# Led_Tree_Main.net
KiCad netlist of a schematic drawn in Altium Designer
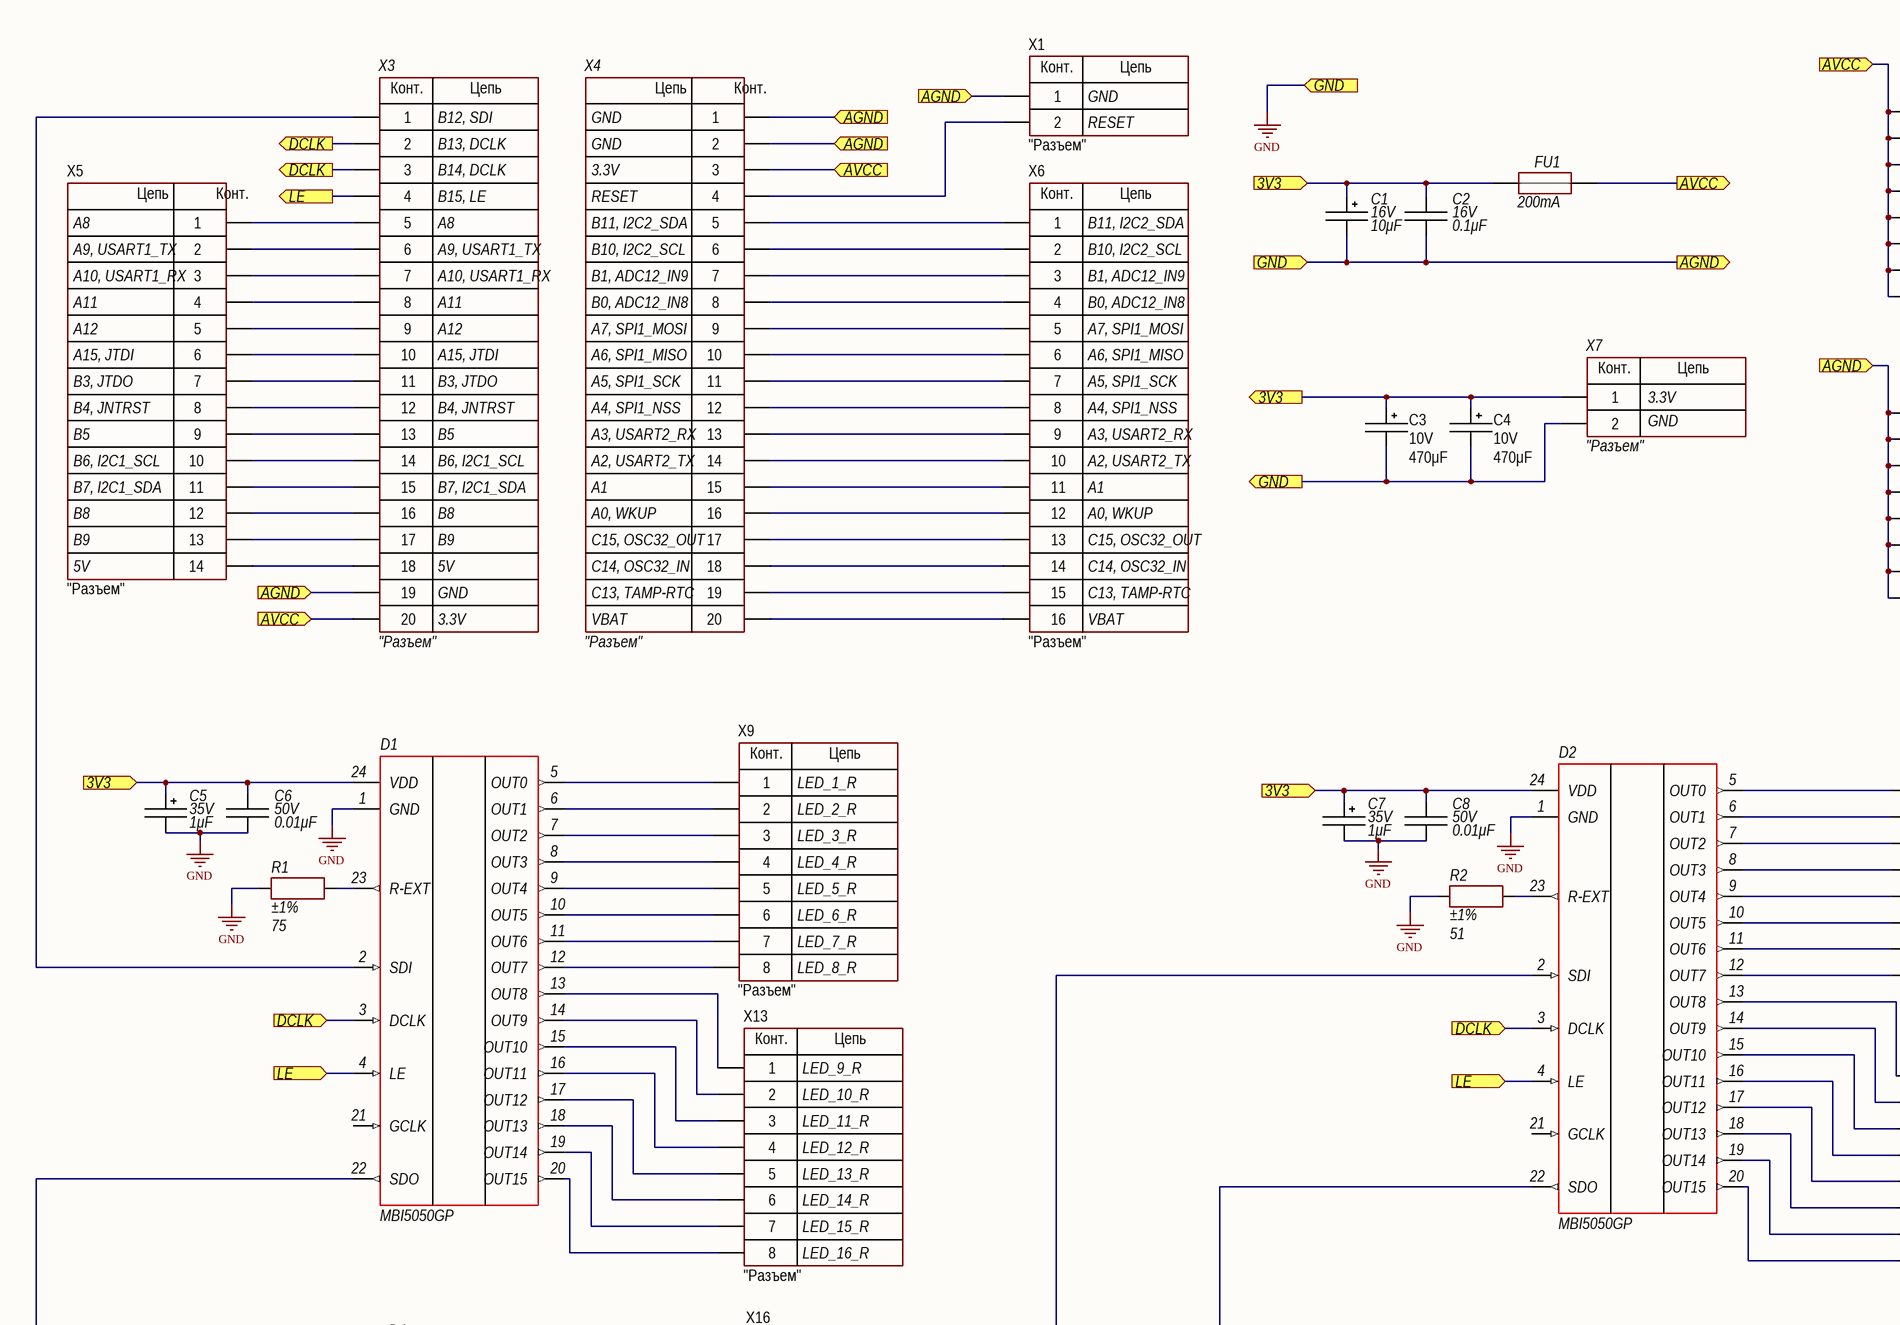
[diagram p0: Led_Tree_Main.SchDoc, top left]
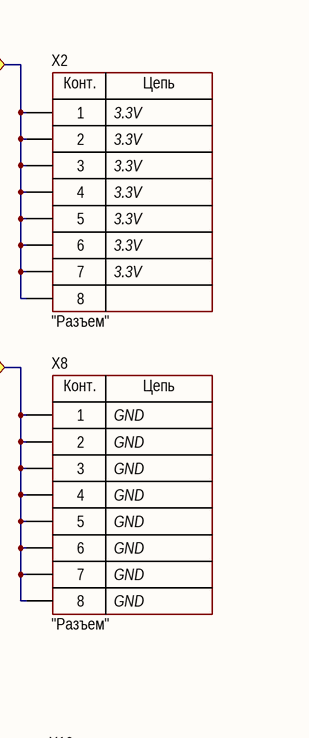
[diagram p1: Led_Tree_Main.SchDoc, top right]
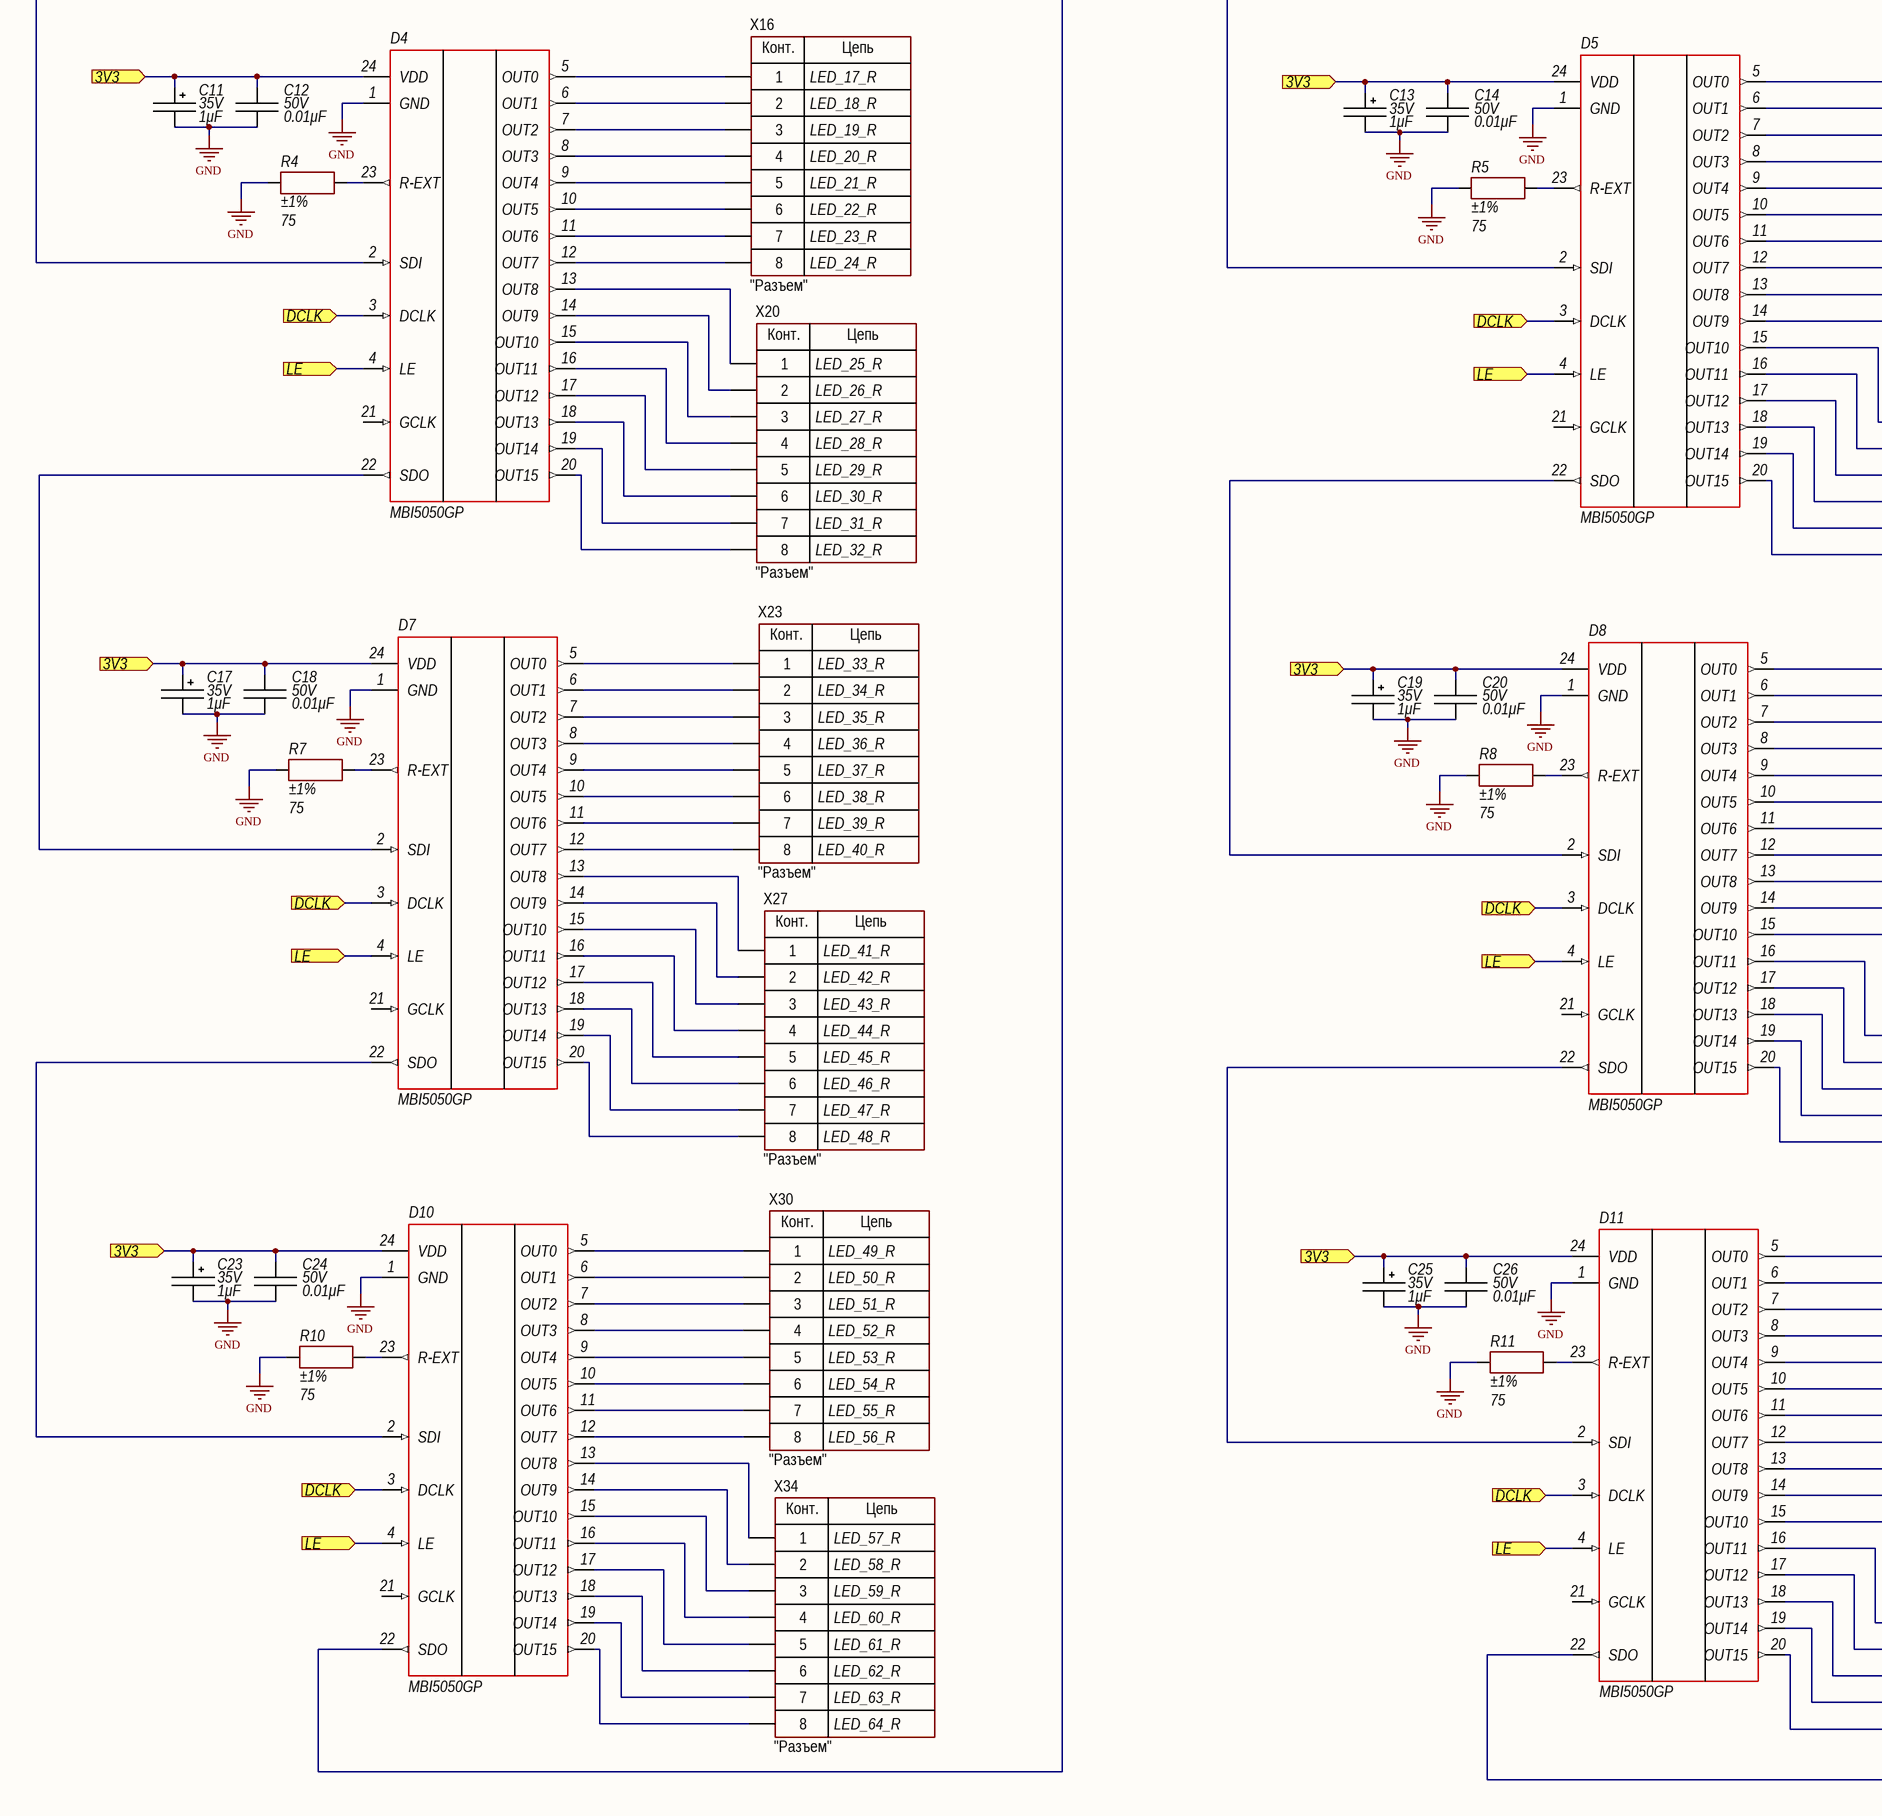
[diagram p2: Led_Tree_Main.SchDoc, bottom left]
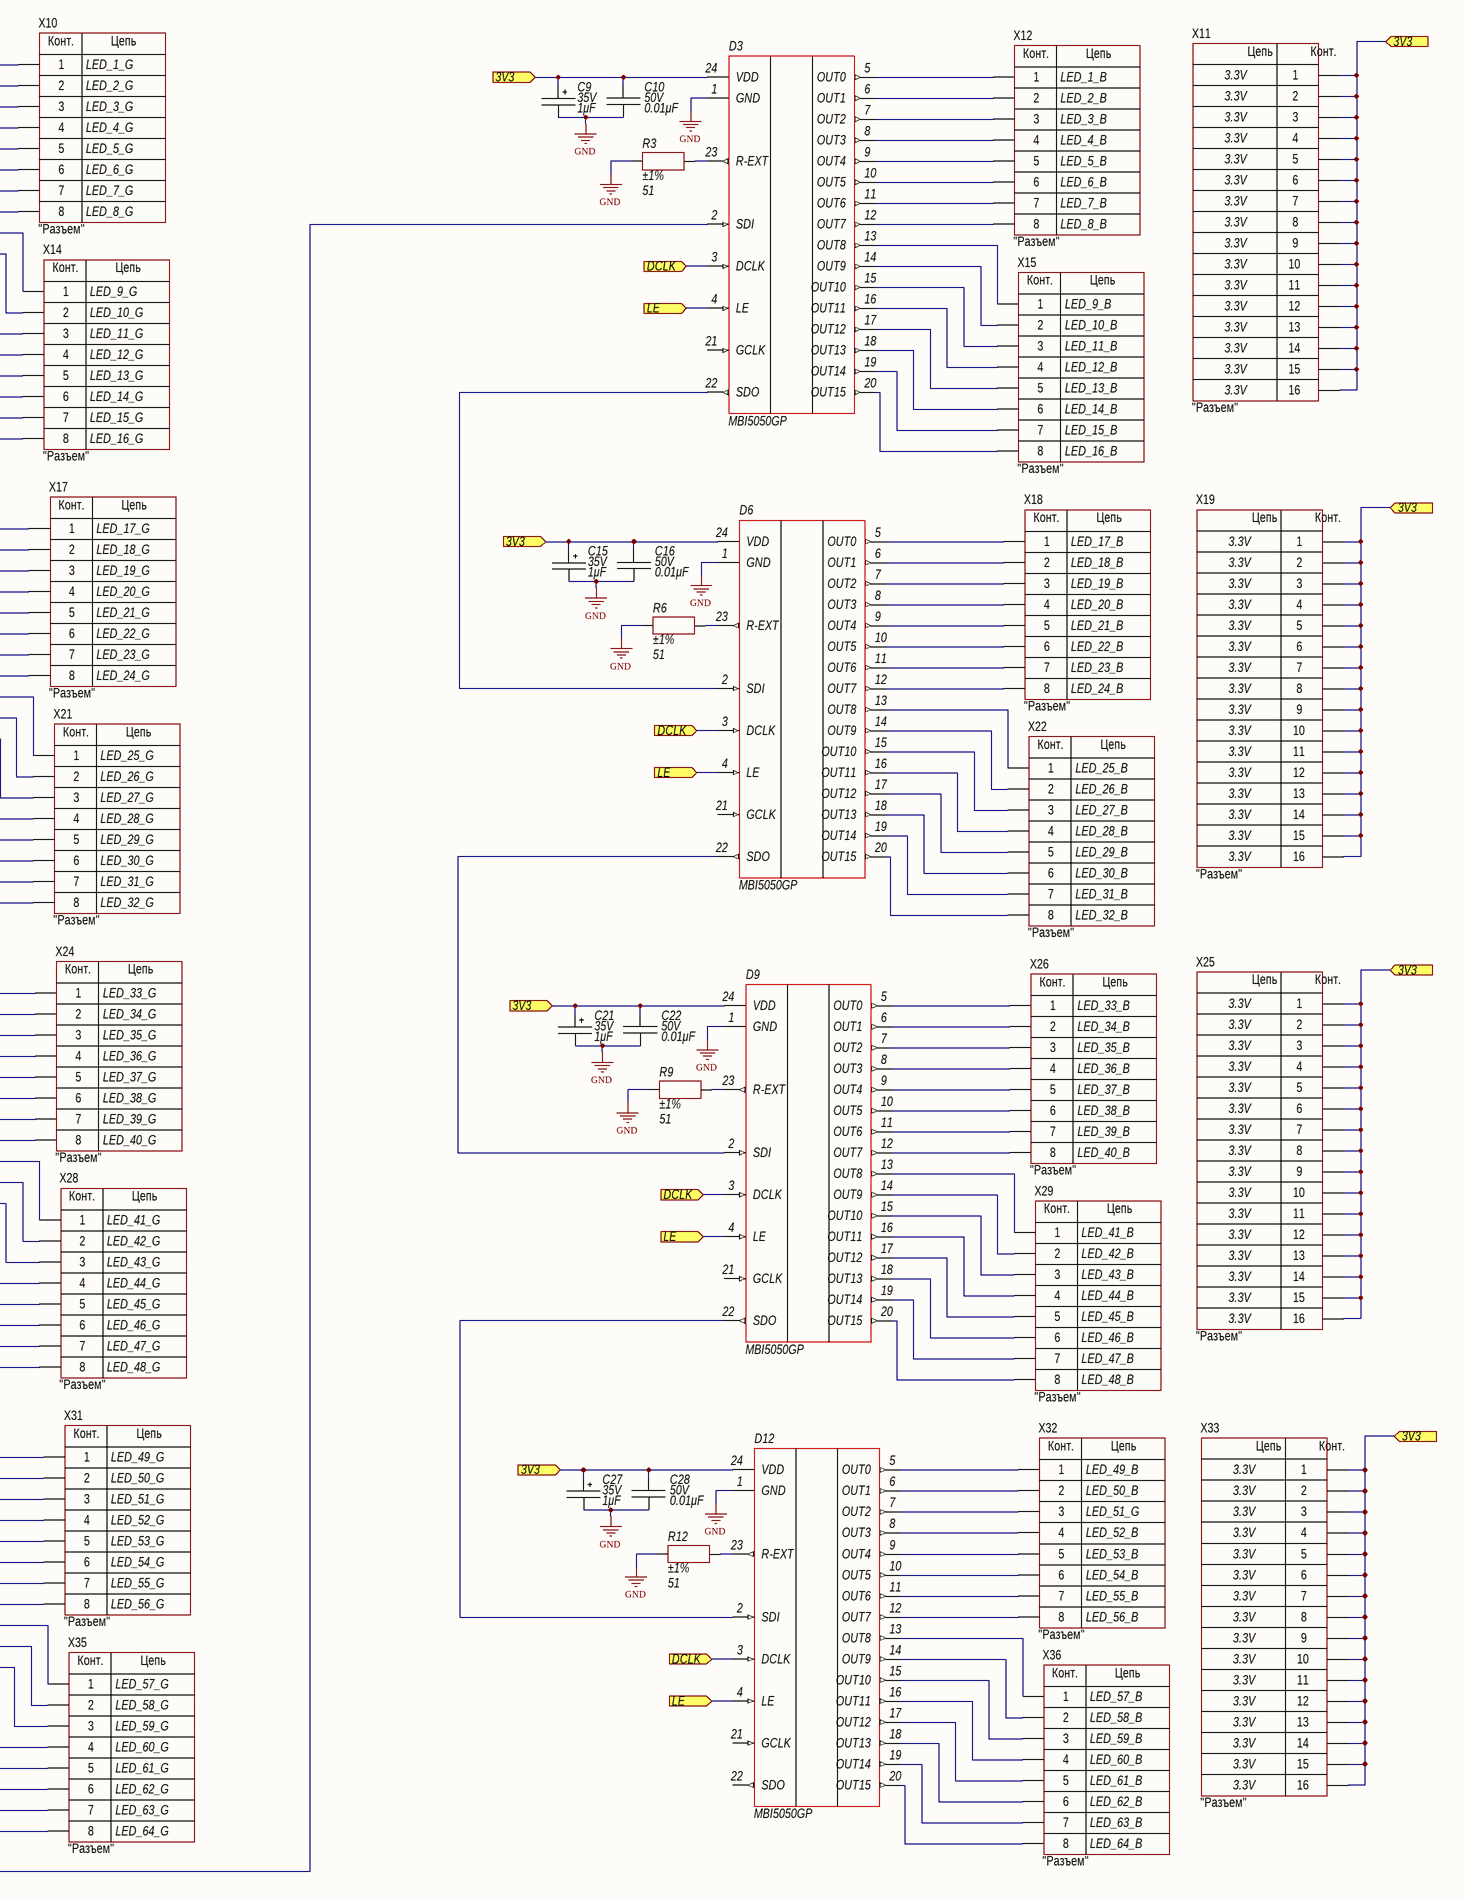
[diagram p3: Led_Tree_Main.SchDoc, bottom right]

(export (version "E")
  (design (tool "Eeschema 10.0.6"))
  (components
    (comp (ref "C1")
      (value "10μF")
      (footprint "CAP: TANTAL-A")
      (fields
        (field (name "MANUFACTURER") "AVX")
        (field (name "PARTNUMBER") "TAJA106K016RNJ")
        (field (name "VALUEMANUFACTURERPARTNUMBER") "Tantalum capacitor, 10μF, 16V, ±10%, 3Ohm, case A (3216), -55...+125°C")
        (field (name "VOLTAGE") "16V")
      )
      (libsource (lib "Capacitor") (part "Tantal_A"))
    )
    (comp (ref "C2")
      (value "0.1μF")
      (footprint "CAP: 0603")
      (fields
        (field (name "MANUFACTURER") "Murata Electronics")
        (field (name "PARTNUMBER") "GRM188R71C104KA01D")
        (field (name "VALUEMANUFACTURERPARTNUMBER") "Ceramic capacitor, 0.1μF, X7R, ±10%, 16V, 0603, -55...+125°C")
        (field (name "VOLTAGE") "16V")
      )
      (libsource (lib "Capacitor") (part "Ceramic_0603"))
    )
    (comp (ref "C3")
      (value "470μF")
      (footprint "CAP: D6.3C2.5H11")
      (fields
        (field (name "MANUFACTURER") "JB")
        (field (name "PARTNUMBER") "JRB1A471M02500630120000B")
        (field (name "VALUEMANUFACTURERPARTNUMBER") "Aluminium capacitor, 470μF, 10V, ±20%, , 14x10x5 mm, -40...+105°C")
        (field (name "VOLTAGE") "10V")
      )
      (libsource (lib "Capacitor") (part "Aluminium"))
    )
    (comp (ref "C4")
      (value "470μF")
      (footprint "CAP: D6.3C2.5H11")
      (fields
        (field (name "MANUFACTURER") "JB")
        (field (name "PARTNUMBER") "JRB1A471M02500630120000B")
        (field (name "VALUEMANUFACTURERPARTNUMBER") "Aluminium capacitor, 470μF, 10V, ±20%, , 14x10x5 mm, -40...+105°C")
        (field (name "VOLTAGE") "10V")
      )
      (libsource (lib "Capacitor") (part "Aluminium"))
    )
    (comp (ref "C5")
      (value "1μF")
      (footprint "CAP: TANTAL-A")
      (fields
        (field (name "MANUFACTURER") "AVX")
        (field (name "PARTNUMBER") "TAJA105K035RNJ")
        (field (name "VALUEMANUFACTURERPARTNUMBER") "Tantalum capacitor, 1μF, 35V, ±10%, 7.5Ohm, case A (3216), -55...+125°C")
        (field (name "VOLTAGE") "35V")
      )
      (libsource (lib "Capacitor") (part "Tantal_A"))
    )
    (comp (ref "C6")
      (value "0.01μF")
      (footprint "CAP: 0603")
      (fields
        (field (name "MANUFACTURER") "Murata Electronics")
        (field (name "PARTNUMBER") "GRM188R71H103KA01D")
        (field (name "VALUEMANUFACTURERPARTNUMBER") "Ceramic capacitor, 0.01μF, X7R, ±10%, 50V, 0603, -55...+125°C")
        (field (name "VOLTAGE") "50V")
      )
      (libsource (lib "Capacitor") (part "Ceramic_0603"))
    )
    (comp (ref "C7")
      (value "1μF")
      (footprint "CAP: TANTAL-A")
      (fields
        (field (name "MANUFACTURER") "AVX")
        (field (name "PARTNUMBER") "TAJA105K035RNJ")
        (field (name "VALUEMANUFACTURERPARTNUMBER") "Tantalum capacitor, 1μF, 35V, ±10%, 7.5Ohm, case A (3216), -55...+125°C")
        (field (name "VOLTAGE") "35V")
      )
      (libsource (lib "Capacitor") (part "Tantal_A"))
    )
    (comp (ref "C8")
      (value "0.01μF")
      (footprint "CAP: 0603")
      (fields
        (field (name "MANUFACTURER") "Murata Electronics")
        (field (name "PARTNUMBER") "GRM188R71H103KA01D")
        (field (name "VALUEMANUFACTURERPARTNUMBER") "Ceramic capacitor, 0.01μF, X7R, ±10%, 50V, 0603, -55...+125°C")
        (field (name "VOLTAGE") "50V")
      )
      (libsource (lib "Capacitor") (part "Ceramic_0603"))
    )
    (comp (ref "C9")
      (value "1μF")
      (footprint "CAP: TANTAL-A")
      (fields
        (field (name "MANUFACTURER") "AVX")
        (field (name "PARTNUMBER") "TAJA105K035RNJ")
        (field (name "VALUEMANUFACTURERPARTNUMBER") "Tantalum capacitor, 1μF, 35V, ±10%, 7.5Ohm, case A (3216), -55...+125°C")
        (field (name "VOLTAGE") "35V")
      )
      (libsource (lib "Capacitor") (part "Tantal_A"))
    )
    (comp (ref "C10")
      (value "0.01μF")
      (footprint "CAP: 0603")
      (fields
        (field (name "MANUFACTURER") "Murata Electronics")
        (field (name "PARTNUMBER") "GRM188R71H103KA01D")
        (field (name "VALUEMANUFACTURERPARTNUMBER") "Ceramic capacitor, 0.01μF, X7R, ±10%, 50V, 0603, -55...+125°C")
        (field (name "VOLTAGE") "50V")
      )
      (libsource (lib "Capacitor") (part "Ceramic_0603"))
    )
    (comp (ref "C11")
      (value "1μF")
      (footprint "CAP: TANTAL-A")
      (fields
        (field (name "MANUFACTURER") "AVX")
        (field (name "PARTNUMBER") "TAJA105K035RNJ")
        (field (name "VALUEMANUFACTURERPARTNUMBER") "Tantalum capacitor, 1μF, 35V, ±10%, 7.5Ohm, case A (3216), -55...+125°C")
        (field (name "VOLTAGE") "35V")
      )
      (libsource (lib "Capacitor") (part "Tantal_A"))
    )
    (comp (ref "C12")
      (value "0.01μF")
      (footprint "CAP: 0603")
      (fields
        (field (name "MANUFACTURER") "Murata Electronics")
        (field (name "PARTNUMBER") "GRM188R71H103KA01D")
        (field (name "VALUEMANUFACTURERPARTNUMBER") "Ceramic capacitor, 0.01μF, X7R, ±10%, 50V, 0603, -55...+125°C")
        (field (name "VOLTAGE") "50V")
      )
      (libsource (lib "Capacitor") (part "Ceramic_0603"))
    )
    (comp (ref "C13")
      (value "1μF")
      (footprint "CAP: TANTAL-A")
      (fields
        (field (name "MANUFACTURER") "AVX")
        (field (name "PARTNUMBER") "TAJA105K035RNJ")
        (field (name "VALUEMANUFACTURERPARTNUMBER") "Tantalum capacitor, 1μF, 35V, ±10%, 7.5Ohm, case A (3216), -55...+125°C")
        (field (name "VOLTAGE") "35V")
      )
      (libsource (lib "Capacitor") (part "Tantal_A"))
    )
    (comp (ref "C14")
      (value "0.01μF")
      (footprint "CAP: 0603")
      (fields
        (field (name "MANUFACTURER") "Murata Electronics")
        (field (name "PARTNUMBER") "GRM188R71H103KA01D")
        (field (name "VALUEMANUFACTURERPARTNUMBER") "Ceramic capacitor, 0.01μF, X7R, ±10%, 50V, 0603, -55...+125°C")
        (field (name "VOLTAGE") "50V")
      )
      (libsource (lib "Capacitor") (part "Ceramic_0603"))
    )
    (comp (ref "C15")
      (value "1μF")
      (footprint "CAP: TANTAL-A")
      (fields
        (field (name "MANUFACTURER") "AVX")
        (field (name "PARTNUMBER") "TAJA105K035RNJ")
        (field (name "VALUEMANUFACTURERPARTNUMBER") "Tantalum capacitor, 1μF, 35V, ±10%, 7.5Ohm, case A (3216), -55...+125°C")
        (field (name "VOLTAGE") "35V")
      )
      (libsource (lib "Capacitor") (part "Tantal_A"))
    )
    (comp (ref "C16")
      (value "0.01μF")
      (footprint "CAP: 0603")
      (fields
        (field (name "MANUFACTURER") "Murata Electronics")
        (field (name "PARTNUMBER") "GRM188R71H103KA01D")
        (field (name "VALUEMANUFACTURERPARTNUMBER") "Ceramic capacitor, 0.01μF, X7R, ±10%, 50V, 0603, -55...+125°C")
        (field (name "VOLTAGE") "50V")
      )
      (libsource (lib "Capacitor") (part "Ceramic_0603"))
    )
    (comp (ref "C17")
      (value "1μF")
      (footprint "CAP: TANTAL-A")
      (fields
        (field (name "MANUFACTURER") "AVX")
        (field (name "PARTNUMBER") "TAJA105K035RNJ")
        (field (name "VALUEMANUFACTURERPARTNUMBER") "Tantalum capacitor, 1μF, 35V, ±10%, 7.5Ohm, case A (3216), -55...+125°C")
        (field (name "VOLTAGE") "35V")
      )
      (libsource (lib "Capacitor") (part "Tantal_A"))
    )
    (comp (ref "C18")
      (value "0.01μF")
      (footprint "CAP: 0603")
      (fields
        (field (name "MANUFACTURER") "Murata Electronics")
        (field (name "PARTNUMBER") "GRM188R71H103KA01D")
        (field (name "VALUEMANUFACTURERPARTNUMBER") "Ceramic capacitor, 0.01μF, X7R, ±10%, 50V, 0603, -55...+125°C")
        (field (name "VOLTAGE") "50V")
      )
      (libsource (lib "Capacitor") (part "Ceramic_0603"))
    )
    (comp (ref "C19")
      (value "1μF")
      (footprint "CAP: TANTAL-A")
      (fields
        (field (name "MANUFACTURER") "AVX")
        (field (name "PARTNUMBER") "TAJA105K035RNJ")
        (field (name "VALUEMANUFACTURERPARTNUMBER") "Tantalum capacitor, 1μF, 35V, ±10%, 7.5Ohm, case A (3216), -55...+125°C")
        (field (name "VOLTAGE") "35V")
      )
      (libsource (lib "Capacitor") (part "Tantal_A"))
    )
    (comp (ref "C20")
      (value "0.01μF")
      (footprint "CAP: 0603")
      (fields
        (field (name "MANUFACTURER") "Murata Electronics")
        (field (name "PARTNUMBER") "GRM188R71H103KA01D")
        (field (name "VALUEMANUFACTURERPARTNUMBER") "Ceramic capacitor, 0.01μF, X7R, ±10%, 50V, 0603, -55...+125°C")
        (field (name "VOLTAGE") "50V")
      )
      (libsource (lib "Capacitor") (part "Ceramic_0603"))
    )
    (comp (ref "C21")
      (value "1μF")
      (footprint "CAP: TANTAL-A")
      (fields
        (field (name "MANUFACTURER") "AVX")
        (field (name "PARTNUMBER") "TAJA105K035RNJ")
        (field (name "VALUEMANUFACTURERPARTNUMBER") "Tantalum capacitor, 1μF, 35V, ±10%, 7.5Ohm, case A (3216), -55...+125°C")
        (field (name "VOLTAGE") "35V")
      )
      (libsource (lib "Capacitor") (part "Tantal_A"))
    )
    (comp (ref "C22")
      (value "0.01μF")
      (footprint "CAP: 0603")
      (fields
        (field (name "MANUFACTURER") "Murata Electronics")
        (field (name "PARTNUMBER") "GRM188R71H103KA01D")
        (field (name "VALUEMANUFACTURERPARTNUMBER") "Ceramic capacitor, 0.01μF, X7R, ±10%, 50V, 0603, -55...+125°C")
        (field (name "VOLTAGE") "50V")
      )
      (libsource (lib "Capacitor") (part "Ceramic_0603"))
    )
    (comp (ref "C23")
      (value "1μF")
      (footprint "CAP: TANTAL-A")
      (fields
        (field (name "MANUFACTURER") "AVX")
        (field (name "PARTNUMBER") "TAJA105K035RNJ")
        (field (name "VALUEMANUFACTURERPARTNUMBER") "Tantalum capacitor, 1μF, 35V, ±10%, 7.5Ohm, case A (3216), -55...+125°C")
        (field (name "VOLTAGE") "35V")
      )
      (libsource (lib "Capacitor") (part "Tantal_A"))
    )
    (comp (ref "C24")
      (value "0.01μF")
      (footprint "CAP: 0603")
      (fields
        (field (name "MANUFACTURER") "Murata Electronics")
        (field (name "PARTNUMBER") "GRM188R71H103KA01D")
        (field (name "VALUEMANUFACTURERPARTNUMBER") "Ceramic capacitor, 0.01μF, X7R, ±10%, 50V, 0603, -55...+125°C")
        (field (name "VOLTAGE") "50V")
      )
      (libsource (lib "Capacitor") (part "Ceramic_0603"))
    )
    (comp (ref "C25")
      (value "1μF")
      (footprint "CAP: TANTAL-A")
      (fields
        (field (name "MANUFACTURER") "AVX")
        (field (name "PARTNUMBER") "TAJA105K035RNJ")
        (field (name "VALUEMANUFACTURERPARTNUMBER") "Tantalum capacitor, 1μF, 35V, ±10%, 7.5Ohm, case A (3216), -55...+125°C")
        (field (name "VOLTAGE") "35V")
      )
      (libsource (lib "Capacitor") (part "Tantal_A"))
    )
    (comp (ref "C26")
      (value "0.01μF")
      (footprint "CAP: 0603")
      (fields
        (field (name "MANUFACTURER") "Murata Electronics")
        (field (name "PARTNUMBER") "GRM188R71H103KA01D")
        (field (name "VALUEMANUFACTURERPARTNUMBER") "Ceramic capacitor, 0.01μF, X7R, ±10%, 50V, 0603, -55...+125°C")
        (field (name "VOLTAGE") "50V")
      )
      (libsource (lib "Capacitor") (part "Ceramic_0603"))
    )
    (comp (ref "C27")
      (value "1μF")
      (footprint "CAP: TANTAL-A")
      (fields
        (field (name "MANUFACTURER") "AVX")
        (field (name "PARTNUMBER") "TAJA105K035RNJ")
        (field (name "VALUEMANUFACTURERPARTNUMBER") "Tantalum capacitor, 1μF, 35V, ±10%, 7.5Ohm, case A (3216), -55...+125°C")
        (field (name "VOLTAGE") "35V")
      )
      (libsource (lib "Capacitor") (part "Tantal_A"))
    )
    (comp (ref "C28")
      (value "0.01μF")
      (footprint "CAP: 0603")
      (fields
        (field (name "MANUFACTURER") "Murata Electronics")
        (field (name "PARTNUMBER") "GRM188R71H103KA01D")
        (field (name "VALUEMANUFACTURERPARTNUMBER") "Ceramic capacitor, 0.01μF, X7R, ±10%, 50V, 0603, -55...+125°C")
        (field (name "VOLTAGE") "50V")
      )
      (libsource (lib "Capacitor") (part "Ceramic_0603"))
    )
    (comp (ref "D1")
      (value "MBI5050GP")
      (footprint "MBI5050GP")
      (description "16ch PWM LED Driver")
      (libsource (lib "LED_Drivers") (part "MBI5050GP"))
    )
    (comp (ref "D2")
      (value "MBI5050GP")
      (footprint "MBI5050GP")
      (description "16ch PWM LED Driver")
      (libsource (lib "LED_Drivers") (part "MBI5050GP"))
    )
    (comp (ref "D3")
      (value "MBI5050GP")
      (footprint "MBI5050GP")
      (description "16ch PWM LED Driver")
      (libsource (lib "LED_Drivers") (part "MBI5050GP"))
    )
    (comp (ref "D4")
      (value "MBI5050GP")
      (footprint "MBI5050GP")
      (description "16ch PWM LED Driver")
      (libsource (lib "LED_Drivers") (part "MBI5050GP"))
    )
    (comp (ref "D5")
      (value "MBI5050GP")
      (footprint "MBI5050GP")
      (description "16ch PWM LED Driver")
      (libsource (lib "LED_Drivers") (part "MBI5050GP"))
    )
    (comp (ref "D6")
      (value "MBI5050GP")
      (footprint "MBI5050GP")
      (description "16ch PWM LED Driver")
      (libsource (lib "LED_Drivers") (part "MBI5050GP"))
    )
    (comp (ref "D7")
      (value "MBI5050GP")
      (footprint "MBI5050GP")
      (description "16ch PWM LED Driver")
      (libsource (lib "LED_Drivers") (part "MBI5050GP"))
    )
    (comp (ref "D8")
      (value "MBI5050GP")
      (footprint "MBI5050GP")
      (description "16ch PWM LED Driver")
      (libsource (lib "LED_Drivers") (part "MBI5050GP"))
    )
    (comp (ref "D9")
      (value "MBI5050GP")
      (footprint "MBI5050GP")
      (description "16ch PWM LED Driver")
      (libsource (lib "LED_Drivers") (part "MBI5050GP"))
    )
    (comp (ref "D10")
      (value "MBI5050GP")
      (footprint "MBI5050GP")
      (description "16ch PWM LED Driver")
      (libsource (lib "LED_Drivers") (part "MBI5050GP"))
    )
    (comp (ref "D11")
      (value "MBI5050GP")
      (footprint "MBI5050GP")
      (description "16ch PWM LED Driver")
      (libsource (lib "LED_Drivers") (part "MBI5050GP"))
    )
    (comp (ref "D12")
      (value "MBI5050GP")
      (footprint "MBI5050GP")
      (description "16ch PWM LED Driver")
      (libsource (lib "LED_Drivers") (part "MBI5050GP"))
    )
    (comp (ref "FU1") (value "200mA") (footprint "1210L020WR") (libsource (lib "Fuses") (part "1210L020WR")))
    (comp (ref "R1")
      (value "75")
      (footprint "RES: 0603")
      (fields
        (field (name "MANUFACTURER") "Yageo")
        (field (name "PARTNUMBER") "RC0603FR-0775RL")
        (field (name "VALUEMANUFACTURERPARTNUMBER") "Resistor film, 75, ±1%, 0603, 0.1W, -55...+155°C")
        (field (name "TOLERANCE") "±1%")
      )
      (libsource (lib "Resistor") (part "Resistor_0603"))
    )
    (comp (ref "R2")
      (value "51")
      (footprint "RES: 0603")
      (fields
        (field (name "MANUFACTURER") "Yageo")
        (field (name "PARTNUMBER") "RC0603FR-0751RL")
        (field (name "VALUEMANUFACTURERPARTNUMBER") "Resistor film, 51, ±1%, 0603, 0.1W, -55...+155°C")
        (field (name "TOLERANCE") "±1%")
      )
      (libsource (lib "Resistor") (part "Resistor_0603"))
    )
    (comp (ref "R3")
      (value "51")
      (footprint "RES: 0603")
      (fields
        (field (name "MANUFACTURER") "Yageo")
        (field (name "PARTNUMBER") "RC0603FR-0751RL")
        (field (name "VALUEMANUFACTURERPARTNUMBER") "Resistor film, 51, ±1%, 0603, 0.1W, -55...+155°C")
        (field (name "TOLERANCE") "±1%")
      )
      (libsource (lib "Resistor") (part "Resistor_0603"))
    )
    (comp (ref "R4")
      (value "75")
      (footprint "RES: 0603")
      (fields
        (field (name "MANUFACTURER") "Yageo")
        (field (name "PARTNUMBER") "RC0603FR-0775RL")
        (field (name "VALUEMANUFACTURERPARTNUMBER") "Resistor film, 75, ±1%, 0603, 0.1W, -55...+155°C")
        (field (name "TOLERANCE") "±1%")
      )
      (libsource (lib "Resistor") (part "Resistor_0603"))
    )
    (comp (ref "R5")
      (value "75")
      (footprint "RES: 0603")
      (fields
        (field (name "MANUFACTURER") "Yageo")
        (field (name "PARTNUMBER") "RC0603FR-0775RL")
        (field (name "VALUEMANUFACTURERPARTNUMBER") "Resistor film, 75, ±1%, 0603, 0.1W, -55...+155°C")
        (field (name "TOLERANCE") "±1%")
      )
      (libsource (lib "Resistor") (part "Resistor_0603"))
    )
    (comp (ref "R6")
      (value "51")
      (footprint "RES: 0603")
      (fields
        (field (name "MANUFACTURER") "Yageo")
        (field (name "PARTNUMBER") "RC0603FR-0751RL")
        (field (name "VALUEMANUFACTURERPARTNUMBER") "Resistor film, 51, ±1%, 0603, 0.1W, -55...+155°C")
        (field (name "TOLERANCE") "±1%")
      )
      (libsource (lib "Resistor") (part "Resistor_0603"))
    )
    (comp (ref "R7")
      (value "75")
      (footprint "RES: 0603")
      (fields
        (field (name "MANUFACTURER") "Yageo")
        (field (name "PARTNUMBER") "RC0603FR-0775RL")
        (field (name "VALUEMANUFACTURERPARTNUMBER") "Resistor film, 75, ±1%, 0603, 0.1W, -55...+155°C")
        (field (name "TOLERANCE") "±1%")
      )
      (libsource (lib "Resistor") (part "Resistor_0603"))
    )
    (comp (ref "R8")
      (value "75")
      (footprint "RES: 0603")
      (fields
        (field (name "MANUFACTURER") "Yageo")
        (field (name "PARTNUMBER") "RC0603FR-0775RL")
        (field (name "VALUEMANUFACTURERPARTNUMBER") "Resistor film, 75, ±1%, 0603, 0.1W, -55...+155°C")
        (field (name "TOLERANCE") "±1%")
      )
      (libsource (lib "Resistor") (part "Resistor_0603"))
    )
    (comp (ref "R9")
      (value "51")
      (footprint "RES: 0603")
      (fields
        (field (name "MANUFACTURER") "Yageo")
        (field (name "PARTNUMBER") "RC0603FR-0751RL")
        (field (name "VALUEMANUFACTURERPARTNUMBER") "Resistor film, 51, ±1%, 0603, 0.1W, -55...+155°C")
        (field (name "TOLERANCE") "±1%")
      )
      (libsource (lib "Resistor") (part "Resistor_0603"))
    )
    (comp (ref "R10")
      (value "75")
      (footprint "RES: 0603")
      (fields
        (field (name "MANUFACTURER") "Yageo")
        (field (name "PARTNUMBER") "RC0603FR-0775RL")
        (field (name "VALUEMANUFACTURERPARTNUMBER") "Resistor film, 75, ±1%, 0603, 0.1W, -55...+155°C")
        (field (name "TOLERANCE") "±1%")
      )
      (libsource (lib "Resistor") (part "Resistor_0603"))
    )
    (comp (ref "R11")
      (value "75")
      (footprint "RES: 0603")
      (fields
        (field (name "MANUFACTURER") "Yageo")
        (field (name "PARTNUMBER") "RC0603FR-0775RL")
        (field (name "VALUEMANUFACTURERPARTNUMBER") "Resistor film, 75, ±1%, 0603, 0.1W, -55...+155°C")
        (field (name "TOLERANCE") "±1%")
      )
      (libsource (lib "") (part "Resistor_0603_1"))
    )
    (comp (ref "R12")
      (value "51")
      (footprint "RES: 0603")
      (fields
        (field (name "MANUFACTURER") "Yageo")
        (field (name "PARTNUMBER") "RC0603FR-0751RL")
        (field (name "VALUEMANUFACTURERPARTNUMBER") "Resistor film, 51, ±1%, 0603, 0.1W, -55...+155°C")
        (field (name "TOLERANCE") "±1%")
      )
      (libsource (lib "Resistor") (part "Resistor_0603"))
    )
    (comp (ref "X1")
      (value "~")
      (footprint "CON: PLS-2")
      (fields
        (field (name "MANUFACTURER") "Connfly")
        (field (name "VALUEMANUFACTURERPARTNUMBER") "Connector, 2pin, 2.54mm, 500VAC, 3A")
        (field (name "PARTNUMBER") "PLS-2")
        (field (name "COMMENTTEXT") "\"Разъем\"")
      )
      (libsource (lib "Connector") (part "PLS-2"))
    )
    (comp (ref "X2")
      (value "~")
      (footprint "CON: PLS-8")
      (fields
        (field (name "MANUFACTURER") "Connfly")
        (field (name "VALUEMANUFACTURERPARTNUMBER") "Connector, 8pin, 2.54mm, 500VAC, 3A")
        (field (name "PARTNUMBER") "PLS-8")
        (field (name "COMMENTTEXT") "\"Разъем\"")
      )
      (libsource (lib "Connector") (part "PLS-8"))
    )
    (comp (ref "X3")
      (value "~")
      (footprint "CON: PBS-20")
      (fields
        (field (name "MANUFACTURER") "Connfly")
        (field (name "PARTNUMBER") "PBS-20")
        (field (name "VALUEMANUFACTURERPARTNUMBER") "Connector, 20pin, 2.54mm, 500VAC, 3A")
        (field (name "COMMENTTEXT") "\"Разъем\"")
      )
      (libsource (lib "Connector") (part "PBS-20"))
    )
    (comp (ref "X4")
      (value "~")
      (footprint "CON: PBS-20")
      (fields
        (field (name "MANUFACTURER") "Connfly")
        (field (name "PARTNUMBER") "PBS-20")
        (field (name "VALUEMANUFACTURERPARTNUMBER") "Connector, 20pin, 2.54mm, 500VAC, 3A")
        (field (name "COMMENTTEXT") "\"Разъем\"")
      )
      (libsource (lib "") (part "PBS-20_1"))
    )
    (comp (ref "X5")
      (value "~")
      (footprint "CON: PLS-14")
      (fields
        (field (name "MANUFACTURER") "Connfly")
        (field (name "VALUEMANUFACTURERPARTNUMBER") "Connector, 14pin, 2.54mm, 500VAC, 3A")
        (field (name "PARTNUMBER") "PLS-14")
        (field (name "COMMENTTEXT") "\"Разъем\"")
      )
      (libsource (lib "Connector") (part "PLS-14"))
    )
    (comp (ref "X6")
      (value "~")
      (footprint "CON: PLS-16")
      (fields
        (field (name "MANUFACTURER") "Connfly")
        (field (name "VALUEMANUFACTURERPARTNUMBER") "Connector, 16pin, 2.54mm, 500VAC, 3A")
        (field (name "PARTNUMBER") "PLS-16")
        (field (name "COMMENTTEXT") "\"Разъем\"")
      )
      (libsource (lib "Connector") (part "PLS-16"))
    )
    (comp (ref "X7")
      (value "~")
      (footprint "CON: TE 1-770166-0")
      (description "Power plug, to board, 2 pins")
      (fields
        (field (name "MANUFACTURER") "TE Connectivity")
        (field (name "PARTNUMBER") "1-770166-0")
        (field (name "COMMENTTEXT") "\"Разъем\"")
      )
      (libsource (lib "Connector") (part "TE 1-770166-0"))
    )
    (comp (ref "X8")
      (value "~")
      (footprint "CON: PLS-8")
      (fields
        (field (name "MANUFACTURER") "Connfly")
        (field (name "VALUEMANUFACTURERPARTNUMBER") "Connector, 8pin, 2.54mm, 500VAC, 3A")
        (field (name "PARTNUMBER") "PLS-8")
        (field (name "COMMENTTEXT") "\"Разъем\"")
      )
      (libsource (lib "Connector") (part "PLS-8"))
    )
    (comp (ref "X9")
      (value "~")
      (footprint "CON: PBS-8")
      (fields
        (field (name "MANUFACTURER") "Connfly")
        (field (name "VALUEMANUFACTURERPARTNUMBER") "Connector, 8pin, 2.54mm, 500VAC, 3A")
        (field (name "PARTNUMBER") "PBS-8")
        (field (name "COMMENTTEXT") "\"Разъем\"")
      )
      (libsource (lib "Connector") (part "PBS-8"))
    )
    (comp (ref "X10")
      (value "~")
      (footprint "CON: PBS-8")
      (fields
        (field (name "MANUFACTURER") "Connfly")
        (field (name "VALUEMANUFACTURERPARTNUMBER") "Connector, 8pin, 2.54mm, 500VAC, 3A")
        (field (name "PARTNUMBER") "PBS-8")
        (field (name "COMMENTTEXT") "\"Разъем\"")
      )
      (libsource (lib "Connector") (part "PBS-8"))
    )
    (comp (ref "X11")
      (value "~")
      (footprint "CON: PBS-16")
      (fields
        (field (name "MANUFACTURER") "Connfly")
        (field (name "VALUEMANUFACTURERPARTNUMBER") "Connector, 16pin, 2.54mm, 500VAC, 3A")
        (field (name "PARTNUMBER") "PBS-16")
        (field (name "COMMENTTEXT") "\"Разъем\"")
      )
      (libsource (lib "Connector") (part "PBS-16"))
    )
    (comp (ref "X12")
      (value "~")
      (footprint "CON: PBS-8")
      (fields
        (field (name "MANUFACTURER") "Connfly")
        (field (name "VALUEMANUFACTURERPARTNUMBER") "Connector, 8pin, 2.54mm, 500VAC, 3A")
        (field (name "PARTNUMBER") "PBS-8")
        (field (name "COMMENTTEXT") "\"Разъем\"")
      )
      (libsource (lib "Connector") (part "PBS-8"))
    )
    (comp (ref "X13")
      (value "~")
      (footprint "CON: PBS-8")
      (fields
        (field (name "MANUFACTURER") "Connfly")
        (field (name "VALUEMANUFACTURERPARTNUMBER") "Connector, 8pin, 2.54mm, 500VAC, 3A")
        (field (name "PARTNUMBER") "PBS-8")
        (field (name "COMMENTTEXT") "\"Разъем\"")
      )
      (libsource (lib "Connector") (part "PBS-8"))
    )
    (comp (ref "X14")
      (value "~")
      (footprint "CON: PBS-8")
      (fields
        (field (name "MANUFACTURER") "Connfly")
        (field (name "VALUEMANUFACTURERPARTNUMBER") "Connector, 8pin, 2.54mm, 500VAC, 3A")
        (field (name "PARTNUMBER") "PBS-8")
        (field (name "COMMENTTEXT") "\"Разъем\"")
      )
      (libsource (lib "Connector") (part "PBS-8"))
    )
    (comp (ref "X15")
      (value "~")
      (footprint "CON: PBS-8")
      (fields
        (field (name "MANUFACTURER") "Connfly")
        (field (name "VALUEMANUFACTURERPARTNUMBER") "Connector, 8pin, 2.54mm, 500VAC, 3A")
        (field (name "PARTNUMBER") "PBS-8")
        (field (name "COMMENTTEXT") "\"Разъем\"")
      )
      (libsource (lib "Connector") (part "PBS-8"))
    )
    (comp (ref "X16")
      (value "~")
      (footprint "CON: PBS-8")
      (fields
        (field (name "MANUFACTURER") "Connfly")
        (field (name "VALUEMANUFACTURERPARTNUMBER") "Connector, 8pin, 2.54mm, 500VAC, 3A")
        (field (name "PARTNUMBER") "PBS-8")
        (field (name "COMMENTTEXT") "\"Разъем\"")
      )
      (libsource (lib "Connector") (part "PBS-8"))
    )
    (comp (ref "X17")
      (value "~")
      (footprint "CON: PBS-8")
      (fields
        (field (name "MANUFACTURER") "Connfly")
        (field (name "VALUEMANUFACTURERPARTNUMBER") "Connector, 8pin, 2.54mm, 500VAC, 3A")
        (field (name "PARTNUMBER") "PBS-8")
        (field (name "COMMENTTEXT") "\"Разъем\"")
      )
      (libsource (lib "Connector") (part "PBS-8"))
    )
    (comp (ref "X18")
      (value "~")
      (footprint "CON: PBS-8")
      (fields
        (field (name "MANUFACTURER") "Connfly")
        (field (name "VALUEMANUFACTURERPARTNUMBER") "Connector, 8pin, 2.54mm, 500VAC, 3A")
        (field (name "PARTNUMBER") "PBS-8")
        (field (name "COMMENTTEXT") "\"Разъем\"")
      )
      (libsource (lib "Connector") (part "PBS-8"))
    )
    (comp (ref "X19")
      (value "~")
      (footprint "CON: PBS-16")
      (fields
        (field (name "MANUFACTURER") "Connfly")
        (field (name "VALUEMANUFACTURERPARTNUMBER") "Connector, 16pin, 2.54mm, 500VAC, 3A")
        (field (name "PARTNUMBER") "PBS-16")
        (field (name "COMMENTTEXT") "\"Разъем\"")
      )
      (libsource (lib "Connector") (part "PBS-16"))
    )
    (comp (ref "X20")
      (value "~")
      (footprint "CON: PBS-8")
      (fields
        (field (name "MANUFACTURER") "Connfly")
        (field (name "VALUEMANUFACTURERPARTNUMBER") "Connector, 8pin, 2.54mm, 500VAC, 3A")
        (field (name "PARTNUMBER") "PBS-8")
        (field (name "COMMENTTEXT") "\"Разъем\"")
      )
      (libsource (lib "Connector") (part "PBS-8"))
    )
    (comp (ref "X21")
      (value "~")
      (footprint "CON: PBS-8")
      (fields
        (field (name "MANUFACTURER") "Connfly")
        (field (name "VALUEMANUFACTURERPARTNUMBER") "Connector, 8pin, 2.54mm, 500VAC, 3A")
        (field (name "PARTNUMBER") "PBS-8")
        (field (name "COMMENTTEXT") "\"Разъем\"")
      )
      (libsource (lib "Connector") (part "PBS-8"))
    )
    (comp (ref "X22")
      (value "~")
      (footprint "CON: PBS-8")
      (fields
        (field (name "MANUFACTURER") "Connfly")
        (field (name "VALUEMANUFACTURERPARTNUMBER") "Connector, 8pin, 2.54mm, 500VAC, 3A")
        (field (name "PARTNUMBER") "PBS-8")
        (field (name "COMMENTTEXT") "\"Разъем\"")
      )
      (libsource (lib "Connector") (part "PBS-8"))
    )
    (comp (ref "X23")
      (value "~")
      (footprint "CON: PBS-8")
      (fields
        (field (name "MANUFACTURER") "Connfly")
        (field (name "VALUEMANUFACTURERPARTNUMBER") "Connector, 8pin, 2.54mm, 500VAC, 3A")
        (field (name "PARTNUMBER") "PBS-8")
        (field (name "COMMENTTEXT") "\"Разъем\"")
      )
      (libsource (lib "Connector") (part "PBS-8"))
    )
    (comp (ref "X24")
      (value "~")
      (footprint "CON: PBS-8")
      (fields
        (field (name "MANUFACTURER") "Connfly")
        (field (name "VALUEMANUFACTURERPARTNUMBER") "Connector, 8pin, 2.54mm, 500VAC, 3A")
        (field (name "PARTNUMBER") "PBS-8")
        (field (name "COMMENTTEXT") "\"Разъем\"")
      )
      (libsource (lib "Connector") (part "PBS-8"))
    )
    (comp (ref "X25")
      (value "~")
      (footprint "CON: PBS-16")
      (fields
        (field (name "MANUFACTURER") "Connfly")
        (field (name "VALUEMANUFACTURERPARTNUMBER") "Connector, 16pin, 2.54mm, 500VAC, 3A")
        (field (name "PARTNUMBER") "PBS-16")
        (field (name "COMMENTTEXT") "\"Разъем\"")
      )
      (libsource (lib "Connector") (part "PBS-16"))
    )
    (comp (ref "X26")
      (value "~")
      (footprint "CON: PBS-8")
      (fields
        (field (name "MANUFACTURER") "Connfly")
        (field (name "VALUEMANUFACTURERPARTNUMBER") "Connector, 8pin, 2.54mm, 500VAC, 3A")
        (field (name "PARTNUMBER") "PBS-8")
        (field (name "COMMENTTEXT") "\"Разъем\"")
      )
      (libsource (lib "Connector") (part "PBS-8"))
    )
    (comp (ref "X27")
      (value "~")
      (footprint "CON: PBS-8")
      (fields
        (field (name "MANUFACTURER") "Connfly")
        (field (name "VALUEMANUFACTURERPARTNUMBER") "Connector, 8pin, 2.54mm, 500VAC, 3A")
        (field (name "PARTNUMBER") "PBS-8")
        (field (name "COMMENTTEXT") "\"Разъем\"")
      )
      (libsource (lib "Connector") (part "PBS-8"))
    )
    (comp (ref "X28")
      (value "~")
      (footprint "CON: PBS-8")
      (fields
        (field (name "MANUFACTURER") "Connfly")
        (field (name "VALUEMANUFACTURERPARTNUMBER") "Connector, 8pin, 2.54mm, 500VAC, 3A")
        (field (name "PARTNUMBER") "PBS-8")
        (field (name "COMMENTTEXT") "\"Разъем\"")
      )
      (libsource (lib "Connector") (part "PBS-8"))
    )
    (comp (ref "X29")
      (value "~")
      (footprint "CON: PBS-8")
      (fields
        (field (name "MANUFACTURER") "Connfly")
        (field (name "VALUEMANUFACTURERPARTNUMBER") "Connector, 8pin, 2.54mm, 500VAC, 3A")
        (field (name "PARTNUMBER") "PBS-8")
        (field (name "COMMENTTEXT") "\"Разъем\"")
      )
      (libsource (lib "Connector") (part "PBS-8"))
    )
    (comp (ref "X30")
      (value "~")
      (footprint "CON: PBS-8")
      (fields
        (field (name "MANUFACTURER") "Connfly")
        (field (name "VALUEMANUFACTURERPARTNUMBER") "Connector, 8pin, 2.54mm, 500VAC, 3A")
        (field (name "PARTNUMBER") "PBS-8")
        (field (name "COMMENTTEXT") "\"Разъем\"")
      )
      (libsource (lib "Connector") (part "PBS-8"))
    )
    (comp (ref "X31")
      (value "~")
      (footprint "CON: PBS-8")
      (fields
        (field (name "MANUFACTURER") "Connfly")
        (field (name "VALUEMANUFACTURERPARTNUMBER") "Connector, 8pin, 2.54mm, 500VAC, 3A")
        (field (name "PARTNUMBER") "PBS-8")
        (field (name "COMMENTTEXT") "\"Разъем\"")
      )
      (libsource (lib "Connector") (part "PBS-8"))
    )
    (comp (ref "X32")
      (value "~")
      (footprint "CON: PBS-8")
      (fields
        (field (name "MANUFACTURER") "Connfly")
        (field (name "VALUEMANUFACTURERPARTNUMBER") "Connector, 8pin, 2.54mm, 500VAC, 3A")
        (field (name "PARTNUMBER") "PBS-8")
        (field (name "COMMENTTEXT") "\"Разъем\"")
      )
      (libsource (lib "Connector") (part "PBS-8"))
    )
    (comp (ref "X33")
      (value "~")
      (footprint "CON: PBS-16")
      (fields
        (field (name "MANUFACTURER") "Connfly")
        (field (name "VALUEMANUFACTURERPARTNUMBER") "Connector, 16pin, 2.54mm, 500VAC, 3A")
        (field (name "PARTNUMBER") "PBS-16")
        (field (name "COMMENTTEXT") "\"Разъем\"")
      )
      (libsource (lib "Connector") (part "PBS-16"))
    )
    (comp (ref "X34")
      (value "~")
      (footprint "CON: PBS-8")
      (fields
        (field (name "MANUFACTURER") "Connfly")
        (field (name "VALUEMANUFACTURERPARTNUMBER") "Connector, 8pin, 2.54mm, 500VAC, 3A")
        (field (name "PARTNUMBER") "PBS-8")
        (field (name "COMMENTTEXT") "\"Разъем\"")
      )
      (libsource (lib "Connector") (part "PBS-8"))
    )
    (comp (ref "X35")
      (value "~")
      (footprint "CON: PBS-8")
      (fields
        (field (name "MANUFACTURER") "Connfly")
        (field (name "VALUEMANUFACTURERPARTNUMBER") "Connector, 8pin, 2.54mm, 500VAC, 3A")
        (field (name "PARTNUMBER") "PBS-8")
        (field (name "COMMENTTEXT") "\"Разъем\"")
      )
      (libsource (lib "Connector") (part "PBS-8"))
    )
    (comp (ref "X36")
      (value "~")
      (footprint "CON: PBS-8")
      (fields
        (field (name "MANUFACTURER") "Connfly")
        (field (name "VALUEMANUFACTURERPARTNUMBER") "Connector, 8pin, 2.54mm, 500VAC, 3A")
        (field (name "PARTNUMBER") "PBS-8")
        (field (name "COMMENTTEXT") "\"Разъем\"")
      )
      (libsource (lib "Connector") (part "PBS-8"))
    )
  )
  (nets
    (net (code "1") (name "/3V3") (class "Default")
      (node (ref "C1") (pin "1") (pinfunction "1_1") (pintype "power_in"))
      (node (ref "C10") (pin "2") (pinfunction "2_2") (pintype "power_in"))
      (node (ref "C11") (pin "1") (pinfunction "1_1") (pintype "power_in"))
      (node (ref "C12") (pin "2") (pinfunction "2_2") (pintype "power_in"))
      (node (ref "C13") (pin "1") (pinfunction "1_1") (pintype "power_in"))
      (node (ref "C14") (pin "2") (pinfunction "2_2") (pintype "power_in"))
      (node (ref "C15") (pin "1") (pinfunction "1_1") (pintype "power_in"))
      (node (ref "C16") (pin "2") (pinfunction "2_2") (pintype "power_in"))
      (node (ref "C17") (pin "1") (pinfunction "1_1") (pintype "power_in"))
      (node (ref "C18") (pin "2") (pinfunction "2_2") (pintype "power_in"))
      (node (ref "C19") (pin "1") (pinfunction "1_1") (pintype "power_in"))
      (node (ref "C2") (pin "2") (pinfunction "2_2") (pintype "power_in"))
      (node (ref "C20") (pin "2") (pinfunction "2_2") (pintype "power_in"))
      (node (ref "C21") (pin "1") (pinfunction "1_1") (pintype "power_in"))
      (node (ref "C22") (pin "2") (pinfunction "2_2") (pintype "power_in"))
      (node (ref "C23") (pin "1") (pinfunction "1_1") (pintype "power_in"))
      (node (ref "C24") (pin "2") (pinfunction "2_2") (pintype "power_in"))
      (node (ref "C25") (pin "1") (pinfunction "1_1") (pintype "power_in"))
      (node (ref "C26") (pin "2") (pinfunction "2_2") (pintype "power_in"))
      (node (ref "C27") (pin "1") (pinfunction "1_1") (pintype "power_in"))
      (node (ref "C28") (pin "2") (pinfunction "2_2") (pintype "power_in"))
      (node (ref "C3") (pin "1") (pinfunction "1_1") (pintype "power_in"))
      (node (ref "C4") (pin "1") (pinfunction "1_1") (pintype "power_in"))
      (node (ref "C5") (pin "1") (pinfunction "1_1") (pintype "power_in"))
      (node (ref "C6") (pin "2") (pinfunction "2_2") (pintype "power_in"))
      (node (ref "C7") (pin "1") (pinfunction "1_1") (pintype "power_in"))
      (node (ref "C8") (pin "2") (pinfunction "2_2") (pintype "power_in"))
      (node (ref "C9") (pin "1") (pinfunction "1_1") (pintype "power_in"))
      (node (ref "D1") (pin "24") (pinfunction "VDD_24") (pintype "power_in"))
      (node (ref "D10") (pin "24") (pinfunction "VDD_24") (pintype "power_in"))
      (node (ref "D11") (pin "24") (pinfunction "VDD_24") (pintype "power_in"))
      (node (ref "D12") (pin "24") (pinfunction "VDD_24") (pintype "power_in"))
      (node (ref "D2") (pin "24") (pinfunction "VDD_24") (pintype "power_in"))
      (node (ref "D3") (pin "24") (pinfunction "VDD_24") (pintype "power_in"))
      (node (ref "D4") (pin "24") (pinfunction "VDD_24") (pintype "power_in"))
      (node (ref "D5") (pin "24") (pinfunction "VDD_24") (pintype "power_in"))
      (node (ref "D6") (pin "24") (pinfunction "VDD_24") (pintype "power_in"))
      (node (ref "D7") (pin "24") (pinfunction "VDD_24") (pintype "power_in"))
      (node (ref "D8") (pin "24") (pinfunction "VDD_24") (pintype "power_in"))
      (node (ref "D9") (pin "24") (pinfunction "VDD_24") (pintype "power_in"))
      (node (ref "FU1") (pin "1") (pintype "passive"))
      (node (ref "X11") (pin "1") (pinfunction "1_1") (pintype "passive"))
      (node (ref "X11") (pin "10") (pinfunction "10_10") (pintype "power_in"))
      (node (ref "X11") (pin "11") (pinfunction "11_11") (pintype "power_in"))
      (node (ref "X11") (pin "12") (pinfunction "12_12") (pintype "power_in"))
      (node (ref "X11") (pin "13") (pinfunction "13_13") (pintype "power_in"))
      (node (ref "X11") (pin "14") (pinfunction "14_14") (pintype "power_in"))
      (node (ref "X11") (pin "15") (pinfunction "15_15") (pintype "power_in"))
      (node (ref "X11") (pin "16") (pinfunction "16_16") (pintype "power_in"))
      (node (ref "X11") (pin "2") (pinfunction "2_2") (pintype "passive"))
      (node (ref "X11") (pin "3") (pinfunction "3_3") (pintype "power_in"))
      (node (ref "X11") (pin "4") (pinfunction "4_4") (pintype "power_in"))
      (node (ref "X11") (pin "5") (pinfunction "5_5") (pintype "power_in"))
      (node (ref "X11") (pin "6") (pinfunction "6_6") (pintype "power_in"))
      (node (ref "X11") (pin "7") (pinfunction "7_7") (pintype "power_in"))
      (node (ref "X11") (pin "8") (pinfunction "8_8") (pintype "power_in"))
      (node (ref "X11") (pin "9") (pinfunction "9_9") (pintype "power_in"))
      (node (ref "X19") (pin "1") (pinfunction "1_1") (pintype "passive"))
      (node (ref "X19") (pin "10") (pinfunction "10_10") (pintype "power_in"))
      (node (ref "X19") (pin "11") (pinfunction "11_11") (pintype "power_in"))
      (node (ref "X19") (pin "12") (pinfunction "12_12") (pintype "power_in"))
      (node (ref "X19") (pin "13") (pinfunction "13_13") (pintype "power_in"))
      (node (ref "X19") (pin "14") (pinfunction "14_14") (pintype "power_in"))
      (node (ref "X19") (pin "15") (pinfunction "15_15") (pintype "power_in"))
      (node (ref "X19") (pin "16") (pinfunction "16_16") (pintype "power_in"))
      (node (ref "X19") (pin "2") (pinfunction "2_2") (pintype "passive"))
      (node (ref "X19") (pin "3") (pinfunction "3_3") (pintype "power_in"))
      (node (ref "X19") (pin "4") (pinfunction "4_4") (pintype "power_in"))
      (node (ref "X19") (pin "5") (pinfunction "5_5") (pintype "power_in"))
      (node (ref "X19") (pin "6") (pinfunction "6_6") (pintype "power_in"))
      (node (ref "X19") (pin "7") (pinfunction "7_7") (pintype "power_in"))
      (node (ref "X19") (pin "8") (pinfunction "8_8") (pintype "power_in"))
      (node (ref "X19") (pin "9") (pinfunction "9_9") (pintype "power_in"))
      (node (ref "X25") (pin "1") (pinfunction "1_1") (pintype "passive"))
      (node (ref "X25") (pin "10") (pinfunction "10_10") (pintype "power_in"))
      (node (ref "X25") (pin "11") (pinfunction "11_11") (pintype "power_in"))
      (node (ref "X25") (pin "12") (pinfunction "12_12") (pintype "power_in"))
      (node (ref "X25") (pin "13") (pinfunction "13_13") (pintype "power_in"))
      (node (ref "X25") (pin "14") (pinfunction "14_14") (pintype "power_in"))
      (node (ref "X25") (pin "15") (pinfunction "15_15") (pintype "power_in"))
      (node (ref "X25") (pin "16") (pinfunction "16_16") (pintype "power_in"))
      (node (ref "X25") (pin "2") (pinfunction "2_2") (pintype "passive"))
      (node (ref "X25") (pin "3") (pinfunction "3_3") (pintype "power_in"))
      (node (ref "X25") (pin "4") (pinfunction "4_4") (pintype "power_in"))
      (node (ref "X25") (pin "5") (pinfunction "5_5") (pintype "power_in"))
      (node (ref "X25") (pin "6") (pinfunction "6_6") (pintype "power_in"))
      (node (ref "X25") (pin "7") (pinfunction "7_7") (pintype "power_in"))
      (node (ref "X25") (pin "8") (pinfunction "8_8") (pintype "power_in"))
      (node (ref "X25") (pin "9") (pinfunction "9_9") (pintype "power_in"))
      (node (ref "X33") (pin "1") (pinfunction "1_1") (pintype "passive"))
      (node (ref "X33") (pin "10") (pinfunction "10_10") (pintype "power_in"))
      (node (ref "X33") (pin "11") (pinfunction "11_11") (pintype "power_in"))
      (node (ref "X33") (pin "12") (pinfunction "12_12") (pintype "power_in"))
      (node (ref "X33") (pin "13") (pinfunction "13_13") (pintype "power_in"))
      (node (ref "X33") (pin "14") (pinfunction "14_14") (pintype "power_in"))
      (node (ref "X33") (pin "15") (pinfunction "15_15") (pintype "power_in"))
      (node (ref "X33") (pin "16") (pinfunction "16_16") (pintype "power_in"))
      (node (ref "X33") (pin "2") (pinfunction "2_2") (pintype "passive"))
      (node (ref "X33") (pin "3") (pinfunction "3_3") (pintype "power_in"))
      (node (ref "X33") (pin "4") (pinfunction "4_4") (pintype "power_in"))
      (node (ref "X33") (pin "5") (pinfunction "5_5") (pintype "power_in"))
      (node (ref "X33") (pin "6") (pinfunction "6_6") (pintype "power_in"))
      (node (ref "X33") (pin "7") (pinfunction "7_7") (pintype "power_in"))
      (node (ref "X33") (pin "8") (pinfunction "8_8") (pintype "power_in"))
      (node (ref "X33") (pin "9") (pinfunction "9_9") (pintype "power_in"))
      (node (ref "X7") (pin "1") (pinfunction "1_1") (pintype "power_in"))
    )
    (net (code "2") (name "/AVCC") (class "Default")
      (node (ref "FU1") (pin "2") (pintype "passive"))
      (node (ref "X2") (pin "1") (pinfunction "1_1") (pintype "passive"))
      (node (ref "X2") (pin "2") (pinfunction "2_2") (pintype "passive"))
      (node (ref "X2") (pin "3") (pinfunction "3_3") (pintype "power_in"))
      (node (ref "X2") (pin "4") (pinfunction "4_4") (pintype "power_in"))
      (node (ref "X2") (pin "5") (pinfunction "5_5") (pintype "power_in"))
      (node (ref "X2") (pin "6") (pinfunction "6_6") (pintype "power_in"))
      (node (ref "X2") (pin "7") (pinfunction "7_7") (pintype "power_in"))
      (node (ref "X2") (pin "8") (pinfunction "8_8") (pintype "power_in"))
      (node (ref "X3") (pin "20") (pinfunction "20_20") (pintype "power_in"))
      (node (ref "X4") (pin "3") (pinfunction "3_3") (pintype "power_in"))
    )
    (net (code "3") (name "/DCLK") (class "Default")
      (node (ref "D1") (pin "3") (pinfunction "DCLK_3") (pintype "input"))
      (node (ref "D10") (pin "3") (pinfunction "DCLK_3") (pintype "input"))
      (node (ref "D11") (pin "3") (pinfunction "DCLK_3") (pintype "input"))
      (node (ref "D12") (pin "3") (pinfunction "DCLK_3") (pintype "input"))
      (node (ref "D2") (pin "3") (pinfunction "DCLK_3") (pintype "input"))
      (node (ref "D3") (pin "3") (pinfunction "DCLK_3") (pintype "input"))
      (node (ref "D4") (pin "3") (pinfunction "DCLK_3") (pintype "input"))
      (node (ref "D5") (pin "3") (pinfunction "DCLK_3") (pintype "input"))
      (node (ref "D6") (pin "3") (pinfunction "DCLK_3") (pintype "input"))
      (node (ref "D7") (pin "3") (pinfunction "DCLK_3") (pintype "input"))
      (node (ref "D8") (pin "3") (pinfunction "DCLK_3") (pintype "input"))
      (node (ref "D9") (pin "3") (pinfunction "DCLK_3") (pintype "input"))
      (node (ref "X3") (pin "2") (pinfunction "2_2") (pintype "passive"))
      (node (ref "X3") (pin "3") (pinfunction "3_3") (pintype "power_in"))
    )
    (net (code "4") (name "/LE") (class "Default")
      (node (ref "D1") (pin "4") (pinfunction "LE_4") (pintype "input"))
      (node (ref "D10") (pin "4") (pinfunction "LE_4") (pintype "input"))
      (node (ref "D11") (pin "4") (pinfunction "LE_4") (pintype "input"))
      (node (ref "D12") (pin "4") (pinfunction "LE_4") (pintype "input"))
      (node (ref "D2") (pin "4") (pinfunction "LE_4") (pintype "input"))
      (node (ref "D3") (pin "4") (pinfunction "LE_4") (pintype "input"))
      (node (ref "D4") (pin "4") (pinfunction "LE_4") (pintype "input"))
      (node (ref "D5") (pin "4") (pinfunction "LE_4") (pintype "input"))
      (node (ref "D6") (pin "4") (pinfunction "LE_4") (pintype "input"))
      (node (ref "D7") (pin "4") (pinfunction "LE_4") (pintype "input"))
      (node (ref "D8") (pin "4") (pinfunction "LE_4") (pintype "input"))
      (node (ref "D9") (pin "4") (pinfunction "LE_4") (pintype "input"))
      (node (ref "X3") (pin "4") (pinfunction "4_4") (pintype "power_in"))
    )
    (net (code "5") (name "GND") (class "Default")
      (node (ref "C1") (pin "2") (pinfunction "2_2") (pintype "power_in"))
      (node (ref "C10") (pin "1") (pinfunction "1_1") (pintype "power_in"))
      (node (ref "C11") (pin "2") (pinfunction "2_2") (pintype "power_in"))
      (node (ref "C12") (pin "1") (pinfunction "1_1") (pintype "power_in"))
      (node (ref "C13") (pin "2") (pinfunction "2_2") (pintype "power_in"))
      (node (ref "C14") (pin "1") (pinfunction "1_1") (pintype "power_in"))
      (node (ref "C15") (pin "2") (pinfunction "2_2") (pintype "power_in"))
      (node (ref "C16") (pin "1") (pinfunction "1_1") (pintype "power_in"))
      (node (ref "C17") (pin "2") (pinfunction "2_2") (pintype "power_in"))
      (node (ref "C18") (pin "1") (pinfunction "1_1") (pintype "power_in"))
      (node (ref "C19") (pin "2") (pinfunction "2_2") (pintype "power_in"))
      (node (ref "C2") (pin "1") (pinfunction "1_1") (pintype "power_in"))
      (node (ref "C20") (pin "1") (pinfunction "1_1") (pintype "power_in"))
      (node (ref "C21") (pin "2") (pinfunction "2_2") (pintype "power_in"))
      (node (ref "C22") (pin "1") (pinfunction "1_1") (pintype "power_in"))
      (node (ref "C23") (pin "2") (pinfunction "2_2") (pintype "power_in"))
      (node (ref "C24") (pin "1") (pinfunction "1_1") (pintype "power_in"))
      (node (ref "C25") (pin "2") (pinfunction "2_2") (pintype "power_in"))
      (node (ref "C26") (pin "1") (pinfunction "1_1") (pintype "power_in"))
      (node (ref "C27") (pin "2") (pinfunction "2_2") (pintype "power_in"))
      (node (ref "C28") (pin "1") (pinfunction "1_1") (pintype "power_in"))
      (node (ref "C3") (pin "2") (pinfunction "2_2") (pintype "power_in"))
      (node (ref "C4") (pin "2") (pinfunction "2_2") (pintype "power_in"))
      (node (ref "C5") (pin "2") (pinfunction "2_2") (pintype "power_in"))
      (node (ref "C6") (pin "1") (pinfunction "1_1") (pintype "power_in"))
      (node (ref "C7") (pin "2") (pinfunction "2_2") (pintype "power_in"))
      (node (ref "C8") (pin "1") (pinfunction "1_1") (pintype "power_in"))
      (node (ref "C9") (pin "2") (pinfunction "2_2") (pintype "power_in"))
      (node (ref "D1") (pin "1") (pinfunction "GND_1") (pintype "power_in"))
      (node (ref "D10") (pin "1") (pinfunction "GND_1") (pintype "power_in"))
      (node (ref "D11") (pin "1") (pinfunction "GND_1") (pintype "power_in"))
      (node (ref "D12") (pin "1") (pinfunction "GND_1") (pintype "power_in"))
      (node (ref "D2") (pin "1") (pinfunction "GND_1") (pintype "power_in"))
      (node (ref "D3") (pin "1") (pinfunction "GND_1") (pintype "power_in"))
      (node (ref "D4") (pin "1") (pinfunction "GND_1") (pintype "power_in"))
      (node (ref "D5") (pin "1") (pinfunction "GND_1") (pintype "power_in"))
      (node (ref "D6") (pin "1") (pinfunction "GND_1") (pintype "power_in"))
      (node (ref "D7") (pin "1") (pinfunction "GND_1") (pintype "power_in"))
      (node (ref "D8") (pin "1") (pinfunction "GND_1") (pintype "power_in"))
      (node (ref "D9") (pin "1") (pinfunction "GND_1") (pintype "power_in"))
      (node (ref "R1") (pin "2") (pinfunction "2_2") (pintype "passive"))
      (node (ref "R10") (pin "2") (pinfunction "2_2") (pintype "passive"))
      (node (ref "R11") (pin "2") (pinfunction "2_2") (pintype "passive"))
      (node (ref "R12") (pin "2") (pinfunction "2_2") (pintype "passive"))
      (node (ref "R2") (pin "2") (pinfunction "2_2") (pintype "passive"))
      (node (ref "R3") (pin "2") (pinfunction "2_2") (pintype "passive"))
      (node (ref "R4") (pin "2") (pinfunction "2_2") (pintype "passive"))
      (node (ref "R5") (pin "2") (pinfunction "2_2") (pintype "passive"))
      (node (ref "R6") (pin "2") (pinfunction "2_2") (pintype "passive"))
      (node (ref "R7") (pin "2") (pinfunction "2_2") (pintype "passive"))
      (node (ref "R8") (pin "2") (pinfunction "2_2") (pintype "passive"))
      (node (ref "R9") (pin "2") (pinfunction "2_2") (pintype "passive"))
      (node (ref "X1") (pin "1") (pinfunction "1_1") (pintype "passive"))
      (node (ref "X3") (pin "19") (pinfunction "19_19") (pintype "power_in"))
      (node (ref "X4") (pin "1") (pinfunction "1_1") (pintype "passive"))
      (node (ref "X4") (pin "2") (pinfunction "2_2") (pintype "passive"))
      (node (ref "X7") (pin "2") (pinfunction "2_2") (pintype "power_in"))
      (node (ref "X8") (pin "1") (pinfunction "1_1") (pintype "passive"))
      (node (ref "X8") (pin "2") (pinfunction "2_2") (pintype "passive"))
      (node (ref "X8") (pin "3") (pinfunction "3_3") (pintype "power_in"))
      (node (ref "X8") (pin "4") (pinfunction "4_4") (pintype "power_in"))
      (node (ref "X8") (pin "5") (pinfunction "5_5") (pintype "power_in"))
      (node (ref "X8") (pin "6") (pinfunction "6_6") (pintype "power_in"))
      (node (ref "X8") (pin "7") (pinfunction "7_7") (pintype "power_in"))
      (node (ref "X8") (pin "8") (pinfunction "8_8") (pintype "power_in"))
    )
    (net (code "6") (name "Net-(D1-OUT0)") (class "Default")
      (node (ref "D1") (pin "5") (pinfunction "OUT0_5") (pintype "output"))
      (node (ref "X9") (pin "1") (pinfunction "1_1") (pintype "passive"))
    )
    (net (code "7") (name "Net-(D1-OUT1)") (class "Default")
      (node (ref "D1") (pin "6") (pinfunction "OUT1_6") (pintype "output"))
      (node (ref "X9") (pin "2") (pinfunction "2_2") (pintype "passive"))
    )
    (net (code "8") (name "Net-(D1-OUT2)") (class "Default")
      (node (ref "D1") (pin "7") (pinfunction "OUT2_7") (pintype "output"))
      (node (ref "X9") (pin "3") (pinfunction "3_3") (pintype "power_in"))
    )
    (net (code "9") (name "Net-(D1-OUT3)") (class "Default")
      (node (ref "D1") (pin "8") (pinfunction "OUT3_8") (pintype "output"))
      (node (ref "X9") (pin "4") (pinfunction "4_4") (pintype "power_in"))
    )
    (net (code "10") (name "Net-(D1-OUT4)") (class "Default")
      (node (ref "D1") (pin "9") (pinfunction "OUT4_9") (pintype "output"))
      (node (ref "X9") (pin "5") (pinfunction "5_5") (pintype "power_in"))
    )
    (net (code "11") (name "Net-(D1-OUT5)") (class "Default")
      (node (ref "D1") (pin "10") (pinfunction "OUT5_10") (pintype "output"))
      (node (ref "X9") (pin "6") (pinfunction "6_6") (pintype "power_in"))
    )
    (net (code "12") (name "Net-(D1-OUT6)") (class "Default")
      (node (ref "D1") (pin "11") (pinfunction "OUT6_11") (pintype "output"))
      (node (ref "X9") (pin "7") (pinfunction "7_7") (pintype "power_in"))
    )
    (net (code "13") (name "Net-(D1-OUT7)") (class "Default")
      (node (ref "D1") (pin "12") (pinfunction "OUT7_12") (pintype "output"))
      (node (ref "X9") (pin "8") (pinfunction "8_8") (pintype "power_in"))
    )
    (net (code "14") (name "Net-(D1-OUT8)") (class "Default")
      (node (ref "D1") (pin "13") (pinfunction "OUT8_13") (pintype "output"))
      (node (ref "X13") (pin "1") (pinfunction "1_1") (pintype "passive"))
    )
    (net (code "15") (name "Net-(D1-OUT9)") (class "Default")
      (node (ref "D1") (pin "14") (pinfunction "OUT9_14") (pintype "output"))
      (node (ref "X13") (pin "2") (pinfunction "2_2") (pintype "passive"))
    )
    (net (code "16") (name "Net-(D1-OUT10)") (class "Default")
      (node (ref "D1") (pin "15") (pinfunction "OUT10_15") (pintype "output"))
      (node (ref "X13") (pin "3") (pinfunction "3_3") (pintype "power_in"))
    )
    (net (code "17") (name "Net-(D1-OUT11)") (class "Default")
      (node (ref "D1") (pin "16") (pinfunction "OUT11_16") (pintype "output"))
      (node (ref "X13") (pin "4") (pinfunction "4_4") (pintype "power_in"))
    )
    (net (code "18") (name "Net-(D1-OUT12)") (class "Default")
      (node (ref "D1") (pin "17") (pinfunction "OUT12_17") (pintype "output"))
      (node (ref "X13") (pin "5") (pinfunction "5_5") (pintype "power_in"))
    )
    (net (code "19") (name "Net-(D1-OUT13)") (class "Default")
      (node (ref "D1") (pin "18") (pinfunction "OUT13_18") (pintype "output"))
      (node (ref "X13") (pin "6") (pinfunction "6_6") (pintype "power_in"))
    )
    (net (code "20") (name "Net-(D1-OUT14)") (class "Default")
      (node (ref "D1") (pin "19") (pinfunction "OUT14_19") (pintype "output"))
      (node (ref "X13") (pin "7") (pinfunction "7_7") (pintype "power_in"))
    )
    (net (code "21") (name "Net-(D1-OUT15)") (class "Default")
      (node (ref "D1") (pin "20") (pinfunction "OUT15_20") (pintype "output"))
      (node (ref "X13") (pin "8") (pinfunction "8_8") (pintype "power_in"))
    )
    (net (code "22") (name "Net-(D1-R-EXT)") (class "Default")
      (node (ref "D1") (pin "23") (pinfunction "R-EXT_23") (pintype "output"))
      (node (ref "R1") (pin "1") (pinfunction "1_1") (pintype "passive"))
    )
    (net (code "23") (name "Net-(D1-SDI)") (class "Default")
      (node (ref "D1") (pin "2") (pinfunction "SDI_2") (pintype "input"))
      (node (ref "X3") (pin "1") (pinfunction "1_1") (pintype "passive"))
    )
    (net (code "24") (name "Net-(D1-SDO)") (class "Default")
      (node (ref "D1") (pin "22") (pinfunction "SDO_22") (pintype "output"))
      (node (ref "D4") (pin "2") (pinfunction "SDI_2") (pintype "input"))
    )
    (net (code "25") (name "Net-(D2-OUT0)") (class "Default")
      (node (ref "D2") (pin "5") (pinfunction "OUT0_5") (pintype "output"))
      (node (ref "X10") (pin "1") (pinfunction "1_1") (pintype "passive"))
    )
    (net (code "26") (name "Net-(D2-OUT1)") (class "Default")
      (node (ref "D2") (pin "6") (pinfunction "OUT1_6") (pintype "output"))
      (node (ref "X10") (pin "2") (pinfunction "2_2") (pintype "passive"))
    )
    (net (code "27") (name "Net-(D2-OUT2)") (class "Default")
      (node (ref "D2") (pin "7") (pinfunction "OUT2_7") (pintype "output"))
      (node (ref "X10") (pin "3") (pinfunction "3_3") (pintype "power_in"))
    )
    (net (code "28") (name "Net-(D2-OUT3)") (class "Default")
      (node (ref "D2") (pin "8") (pinfunction "OUT3_8") (pintype "output"))
      (node (ref "X10") (pin "4") (pinfunction "4_4") (pintype "power_in"))
    )
    (net (code "29") (name "Net-(D2-OUT4)") (class "Default")
      (node (ref "D2") (pin "9") (pinfunction "OUT4_9") (pintype "output"))
      (node (ref "X10") (pin "5") (pinfunction "5_5") (pintype "power_in"))
    )
    (net (code "30") (name "Net-(D2-OUT5)") (class "Default")
      (node (ref "D2") (pin "10") (pinfunction "OUT5_10") (pintype "output"))
      (node (ref "X10") (pin "6") (pinfunction "6_6") (pintype "power_in"))
    )
    (net (code "31") (name "Net-(D2-OUT6)") (class "Default")
      (node (ref "D2") (pin "11") (pinfunction "OUT6_11") (pintype "output"))
      (node (ref "X10") (pin "7") (pinfunction "7_7") (pintype "power_in"))
    )
    (net (code "32") (name "Net-(D2-OUT7)") (class "Default")
      (node (ref "D2") (pin "12") (pinfunction "OUT7_12") (pintype "output"))
      (node (ref "X10") (pin "8") (pinfunction "8_8") (pintype "power_in"))
    )
    (net (code "33") (name "Net-(D2-OUT8)") (class "Default")
      (node (ref "D2") (pin "13") (pinfunction "OUT8_13") (pintype "output"))
      (node (ref "X14") (pin "1") (pinfunction "1_1") (pintype "passive"))
    )
    (net (code "34") (name "Net-(D2-OUT9)") (class "Default")
      (node (ref "D2") (pin "14") (pinfunction "OUT9_14") (pintype "output"))
      (node (ref "X14") (pin "2") (pinfunction "2_2") (pintype "passive"))
    )
    (net (code "35") (name "Net-(D2-OUT10)") (class "Default")
      (node (ref "D2") (pin "15") (pinfunction "OUT10_15") (pintype "output"))
      (node (ref "X14") (pin "3") (pinfunction "3_3") (pintype "power_in"))
    )
    (net (code "36") (name "Net-(D2-OUT11)") (class "Default")
      (node (ref "D2") (pin "16") (pinfunction "OUT11_16") (pintype "output"))
      (node (ref "X14") (pin "4") (pinfunction "4_4") (pintype "power_in"))
    )
    (net (code "37") (name "Net-(D2-OUT12)") (class "Default")
      (node (ref "D2") (pin "17") (pinfunction "OUT12_17") (pintype "output"))
      (node (ref "X14") (pin "5") (pinfunction "5_5") (pintype "power_in"))
    )
    (net (code "38") (name "Net-(D2-OUT13)") (class "Default")
      (node (ref "D2") (pin "18") (pinfunction "OUT13_18") (pintype "output"))
      (node (ref "X14") (pin "6") (pinfunction "6_6") (pintype "power_in"))
    )
    (net (code "39") (name "Net-(D2-OUT14)") (class "Default")
      (node (ref "D2") (pin "19") (pinfunction "OUT14_19") (pintype "output"))
      (node (ref "X14") (pin "7") (pinfunction "7_7") (pintype "power_in"))
    )
    (net (code "40") (name "Net-(D2-OUT15)") (class "Default")
      (node (ref "D2") (pin "20") (pinfunction "OUT15_20") (pintype "output"))
      (node (ref "X14") (pin "8") (pinfunction "8_8") (pintype "power_in"))
    )
    (net (code "41") (name "Net-(D2-R-EXT)") (class "Default")
      (node (ref "D2") (pin "23") (pinfunction "R-EXT_23") (pintype "output"))
      (node (ref "R2") (pin "1") (pinfunction "1_1") (pintype "passive"))
    )
    (net (code "42") (name "Net-(D2-SDO)") (class "Default")
      (node (ref "D2") (pin "22") (pinfunction "SDO_22") (pintype "output"))
      (node (ref "D5") (pin "2") (pinfunction "SDI_2") (pintype "input"))
    )
    (net (code "43") (name "Net-(D3-OUT0)") (class "Default")
      (node (ref "D3") (pin "5") (pinfunction "OUT0_5") (pintype "output"))
      (node (ref "X12") (pin "1") (pinfunction "1_1") (pintype "passive"))
    )
    (net (code "44") (name "Net-(D3-OUT1)") (class "Default")
      (node (ref "D3") (pin "6") (pinfunction "OUT1_6") (pintype "output"))
      (node (ref "X12") (pin "2") (pinfunction "2_2") (pintype "passive"))
    )
    (net (code "45") (name "Net-(D3-OUT2)") (class "Default")
      (node (ref "D3") (pin "7") (pinfunction "OUT2_7") (pintype "output"))
      (node (ref "X12") (pin "3") (pinfunction "3_3") (pintype "power_in"))
    )
    (net (code "46") (name "Net-(D3-OUT3)") (class "Default")
      (node (ref "D3") (pin "8") (pinfunction "OUT3_8") (pintype "output"))
      (node (ref "X12") (pin "4") (pinfunction "4_4") (pintype "power_in"))
    )
    (net (code "47") (name "Net-(D3-OUT4)") (class "Default")
      (node (ref "D3") (pin "9") (pinfunction "OUT4_9") (pintype "output"))
      (node (ref "X12") (pin "5") (pinfunction "5_5") (pintype "power_in"))
    )
    (net (code "48") (name "Net-(D3-OUT5)") (class "Default")
      (node (ref "D3") (pin "10") (pinfunction "OUT5_10") (pintype "output"))
      (node (ref "X12") (pin "6") (pinfunction "6_6") (pintype "power_in"))
    )
    (net (code "49") (name "Net-(D3-OUT6)") (class "Default")
      (node (ref "D3") (pin "11") (pinfunction "OUT6_11") (pintype "output"))
      (node (ref "X12") (pin "7") (pinfunction "7_7") (pintype "power_in"))
    )
    (net (code "50") (name "Net-(D3-OUT7)") (class "Default")
      (node (ref "D3") (pin "12") (pinfunction "OUT7_12") (pintype "output"))
      (node (ref "X12") (pin "8") (pinfunction "8_8") (pintype "power_in"))
    )
    (net (code "51") (name "Net-(D3-OUT8)") (class "Default")
      (node (ref "D3") (pin "13") (pinfunction "OUT8_13") (pintype "output"))
      (node (ref "X15") (pin "1") (pinfunction "1_1") (pintype "passive"))
    )
    (net (code "52") (name "Net-(D3-OUT9)") (class "Default")
      (node (ref "D3") (pin "14") (pinfunction "OUT9_14") (pintype "output"))
      (node (ref "X15") (pin "2") (pinfunction "2_2") (pintype "passive"))
    )
    (net (code "53") (name "Net-(D3-OUT10)") (class "Default")
      (node (ref "D3") (pin "15") (pinfunction "OUT10_15") (pintype "output"))
      (node (ref "X15") (pin "3") (pinfunction "3_3") (pintype "power_in"))
    )
    (net (code "54") (name "Net-(D3-OUT11)") (class "Default")
      (node (ref "D3") (pin "16") (pinfunction "OUT11_16") (pintype "output"))
      (node (ref "X15") (pin "4") (pinfunction "4_4") (pintype "power_in"))
    )
    (net (code "55") (name "Net-(D3-OUT12)") (class "Default")
      (node (ref "D3") (pin "17") (pinfunction "OUT12_17") (pintype "output"))
      (node (ref "X15") (pin "5") (pinfunction "5_5") (pintype "power_in"))
    )
    (net (code "56") (name "Net-(D3-OUT13)") (class "Default")
      (node (ref "D3") (pin "18") (pinfunction "OUT13_18") (pintype "output"))
      (node (ref "X15") (pin "6") (pinfunction "6_6") (pintype "power_in"))
    )
    (net (code "57") (name "Net-(D3-OUT14)") (class "Default")
      (node (ref "D3") (pin "19") (pinfunction "OUT14_19") (pintype "output"))
      (node (ref "X15") (pin "7") (pinfunction "7_7") (pintype "power_in"))
    )
    (net (code "58") (name "Net-(D3-OUT15)") (class "Default")
      (node (ref "D3") (pin "20") (pinfunction "OUT15_20") (pintype "output"))
      (node (ref "X15") (pin "8") (pinfunction "8_8") (pintype "power_in"))
    )
    (net (code "59") (name "Net-(D3-R-EXT)") (class "Default")
      (node (ref "D3") (pin "23") (pinfunction "R-EXT_23") (pintype "output"))
      (node (ref "R3") (pin "1") (pinfunction "1_1") (pintype "passive"))
    )
    (net (code "60") (name "Net-(D3-SDO)") (class "Default")
      (node (ref "D3") (pin "22") (pinfunction "SDO_22") (pintype "output"))
      (node (ref "D6") (pin "2") (pinfunction "SDI_2") (pintype "input"))
    )
    (net (code "61") (name "Net-(D4-OUT0)") (class "Default")
      (node (ref "D4") (pin "5") (pinfunction "OUT0_5") (pintype "output"))
      (node (ref "X16") (pin "1") (pinfunction "1_1") (pintype "passive"))
    )
    (net (code "62") (name "Net-(D4-OUT1)") (class "Default")
      (node (ref "D4") (pin "6") (pinfunction "OUT1_6") (pintype "output"))
      (node (ref "X16") (pin "2") (pinfunction "2_2") (pintype "passive"))
    )
    (net (code "63") (name "Net-(D4-OUT2)") (class "Default")
      (node (ref "D4") (pin "7") (pinfunction "OUT2_7") (pintype "output"))
      (node (ref "X16") (pin "3") (pinfunction "3_3") (pintype "power_in"))
    )
    (net (code "64") (name "Net-(D4-OUT3)") (class "Default")
      (node (ref "D4") (pin "8") (pinfunction "OUT3_8") (pintype "output"))
      (node (ref "X16") (pin "4") (pinfunction "4_4") (pintype "power_in"))
    )
    (net (code "65") (name "Net-(D4-OUT4)") (class "Default")
      (node (ref "D4") (pin "9") (pinfunction "OUT4_9") (pintype "output"))
      (node (ref "X16") (pin "5") (pinfunction "5_5") (pintype "power_in"))
    )
    (net (code "66") (name "Net-(D4-OUT5)") (class "Default")
      (node (ref "D4") (pin "10") (pinfunction "OUT5_10") (pintype "output"))
      (node (ref "X16") (pin "6") (pinfunction "6_6") (pintype "power_in"))
    )
    (net (code "67") (name "Net-(D4-OUT6)") (class "Default")
      (node (ref "D4") (pin "11") (pinfunction "OUT6_11") (pintype "output"))
      (node (ref "X16") (pin "7") (pinfunction "7_7") (pintype "power_in"))
    )
    (net (code "68") (name "Net-(D4-OUT7)") (class "Default")
      (node (ref "D4") (pin "12") (pinfunction "OUT7_12") (pintype "output"))
      (node (ref "X16") (pin "8") (pinfunction "8_8") (pintype "power_in"))
    )
    (net (code "69") (name "Net-(D4-OUT8)") (class "Default")
      (node (ref "D4") (pin "13") (pinfunction "OUT8_13") (pintype "output"))
      (node (ref "X20") (pin "1") (pinfunction "1_1") (pintype "passive"))
    )
    (net (code "70") (name "Net-(D4-OUT9)") (class "Default")
      (node (ref "D4") (pin "14") (pinfunction "OUT9_14") (pintype "output"))
      (node (ref "X20") (pin "2") (pinfunction "2_2") (pintype "passive"))
    )
    (net (code "71") (name "Net-(D4-OUT10)") (class "Default")
      (node (ref "D4") (pin "15") (pinfunction "OUT10_15") (pintype "output"))
      (node (ref "X20") (pin "3") (pinfunction "3_3") (pintype "power_in"))
    )
    (net (code "72") (name "Net-(D4-OUT11)") (class "Default")
      (node (ref "D4") (pin "16") (pinfunction "OUT11_16") (pintype "output"))
      (node (ref "X20") (pin "4") (pinfunction "4_4") (pintype "power_in"))
    )
    (net (code "73") (name "Net-(D4-OUT12)") (class "Default")
      (node (ref "D4") (pin "17") (pinfunction "OUT12_17") (pintype "output"))
      (node (ref "X20") (pin "5") (pinfunction "5_5") (pintype "power_in"))
    )
    (net (code "74") (name "Net-(D4-OUT13)") (class "Default")
      (node (ref "D4") (pin "18") (pinfunction "OUT13_18") (pintype "output"))
      (node (ref "X20") (pin "6") (pinfunction "6_6") (pintype "power_in"))
    )
    (net (code "75") (name "Net-(D4-OUT14)") (class "Default")
      (node (ref "D4") (pin "19") (pinfunction "OUT14_19") (pintype "output"))
      (node (ref "X20") (pin "7") (pinfunction "7_7") (pintype "power_in"))
    )
    (net (code "76") (name "Net-(D4-OUT15)") (class "Default")
      (node (ref "D4") (pin "20") (pinfunction "OUT15_20") (pintype "output"))
      (node (ref "X20") (pin "8") (pinfunction "8_8") (pintype "power_in"))
    )
    (net (code "77") (name "Net-(D4-R-EXT)") (class "Default")
      (node (ref "D4") (pin "23") (pinfunction "R-EXT_23") (pintype "output"))
      (node (ref "R4") (pin "1") (pinfunction "1_1") (pintype "passive"))
    )
    (net (code "78") (name "Net-(D4-SDO)") (class "Default")
      (node (ref "D4") (pin "22") (pinfunction "SDO_22") (pintype "output"))
      (node (ref "D7") (pin "2") (pinfunction "SDI_2") (pintype "input"))
    )
    (net (code "79") (name "Net-(D5-OUT0)") (class "Default")
      (node (ref "D5") (pin "5") (pinfunction "OUT0_5") (pintype "output"))
      (node (ref "X17") (pin "1") (pinfunction "1_1") (pintype "passive"))
    )
    (net (code "80") (name "Net-(D5-OUT1)") (class "Default")
      (node (ref "D5") (pin "6") (pinfunction "OUT1_6") (pintype "output"))
      (node (ref "X17") (pin "2") (pinfunction "2_2") (pintype "passive"))
    )
    (net (code "81") (name "Net-(D5-OUT2)") (class "Default")
      (node (ref "D5") (pin "7") (pinfunction "OUT2_7") (pintype "output"))
      (node (ref "X17") (pin "3") (pinfunction "3_3") (pintype "power_in"))
    )
    (net (code "82") (name "Net-(D5-OUT3)") (class "Default")
      (node (ref "D5") (pin "8") (pinfunction "OUT3_8") (pintype "output"))
      (node (ref "X17") (pin "4") (pinfunction "4_4") (pintype "power_in"))
    )
    (net (code "83") (name "Net-(D5-OUT4)") (class "Default")
      (node (ref "D5") (pin "9") (pinfunction "OUT4_9") (pintype "output"))
      (node (ref "X17") (pin "5") (pinfunction "5_5") (pintype "power_in"))
    )
    (net (code "84") (name "Net-(D5-OUT5)") (class "Default")
      (node (ref "D5") (pin "10") (pinfunction "OUT5_10") (pintype "output"))
      (node (ref "X17") (pin "6") (pinfunction "6_6") (pintype "power_in"))
    )
    (net (code "85") (name "Net-(D5-OUT6)") (class "Default")
      (node (ref "D5") (pin "11") (pinfunction "OUT6_11") (pintype "output"))
      (node (ref "X17") (pin "7") (pinfunction "7_7") (pintype "power_in"))
    )
    (net (code "86") (name "Net-(D5-OUT7)") (class "Default")
      (node (ref "D5") (pin "12") (pinfunction "OUT7_12") (pintype "output"))
      (node (ref "X17") (pin "8") (pinfunction "8_8") (pintype "power_in"))
    )
    (net (code "87") (name "Net-(D5-OUT8)") (class "Default")
      (node (ref "D5") (pin "13") (pinfunction "OUT8_13") (pintype "output"))
      (node (ref "X21") (pin "1") (pinfunction "1_1") (pintype "passive"))
    )
    (net (code "88") (name "Net-(D5-OUT9)") (class "Default")
      (node (ref "D5") (pin "14") (pinfunction "OUT9_14") (pintype "output"))
      (node (ref "X21") (pin "2") (pinfunction "2_2") (pintype "passive"))
    )
    (net (code "89") (name "Net-(D5-OUT10)") (class "Default")
      (node (ref "D5") (pin "15") (pinfunction "OUT10_15") (pintype "output"))
      (node (ref "X21") (pin "3") (pinfunction "3_3") (pintype "power_in"))
    )
    (net (code "90") (name "Net-(D5-OUT11)") (class "Default")
      (node (ref "D5") (pin "16") (pinfunction "OUT11_16") (pintype "output"))
      (node (ref "X21") (pin "4") (pinfunction "4_4") (pintype "power_in"))
    )
    (net (code "91") (name "Net-(D5-OUT12)") (class "Default")
      (node (ref "D5") (pin "17") (pinfunction "OUT12_17") (pintype "output"))
      (node (ref "X21") (pin "5") (pinfunction "5_5") (pintype "power_in"))
    )
    (net (code "92") (name "Net-(D5-OUT13)") (class "Default")
      (node (ref "D5") (pin "18") (pinfunction "OUT13_18") (pintype "output"))
      (node (ref "X21") (pin "6") (pinfunction "6_6") (pintype "power_in"))
    )
    (net (code "93") (name "Net-(D5-OUT14)") (class "Default")
      (node (ref "D5") (pin "19") (pinfunction "OUT14_19") (pintype "output"))
      (node (ref "X21") (pin "7") (pinfunction "7_7") (pintype "power_in"))
    )
    (net (code "94") (name "Net-(D5-OUT15)") (class "Default")
      (node (ref "D5") (pin "20") (pinfunction "OUT15_20") (pintype "output"))
      (node (ref "X21") (pin "8") (pinfunction "8_8") (pintype "power_in"))
    )
    (net (code "95") (name "Net-(D5-R-EXT)") (class "Default")
      (node (ref "D5") (pin "23") (pinfunction "R-EXT_23") (pintype "output"))
      (node (ref "R5") (pin "1") (pinfunction "1_1") (pintype "passive"))
    )
    (net (code "96") (name "Net-(D5-SDO)") (class "Default")
      (node (ref "D5") (pin "22") (pinfunction "SDO_22") (pintype "output"))
      (node (ref "D8") (pin "2") (pinfunction "SDI_2") (pintype "input"))
    )
    (net (code "97") (name "Net-(D6-OUT0)") (class "Default")
      (node (ref "D6") (pin "5") (pinfunction "OUT0_5") (pintype "output"))
      (node (ref "X18") (pin "1") (pinfunction "1_1") (pintype "passive"))
    )
    (net (code "98") (name "Net-(D6-OUT1)") (class "Default")
      (node (ref "D6") (pin "6") (pinfunction "OUT1_6") (pintype "output"))
      (node (ref "X18") (pin "2") (pinfunction "2_2") (pintype "passive"))
    )
    (net (code "99") (name "Net-(D6-OUT2)") (class "Default")
      (node (ref "D6") (pin "7") (pinfunction "OUT2_7") (pintype "output"))
      (node (ref "X18") (pin "3") (pinfunction "3_3") (pintype "power_in"))
    )
    (net (code "100") (name "Net-(D6-OUT3)") (class "Default")
      (node (ref "D6") (pin "8") (pinfunction "OUT3_8") (pintype "output"))
      (node (ref "X18") (pin "4") (pinfunction "4_4") (pintype "power_in"))
    )
    (net (code "101") (name "Net-(D6-OUT4)") (class "Default")
      (node (ref "D6") (pin "9") (pinfunction "OUT4_9") (pintype "output"))
      (node (ref "X18") (pin "5") (pinfunction "5_5") (pintype "power_in"))
    )
    (net (code "102") (name "Net-(D6-OUT5)") (class "Default")
      (node (ref "D6") (pin "10") (pinfunction "OUT5_10") (pintype "output"))
      (node (ref "X18") (pin "6") (pinfunction "6_6") (pintype "power_in"))
    )
    (net (code "103") (name "Net-(D6-OUT6)") (class "Default")
      (node (ref "D6") (pin "11") (pinfunction "OUT6_11") (pintype "output"))
      (node (ref "X18") (pin "7") (pinfunction "7_7") (pintype "power_in"))
    )
    (net (code "104") (name "Net-(D6-OUT7)") (class "Default")
      (node (ref "D6") (pin "12") (pinfunction "OUT7_12") (pintype "output"))
      (node (ref "X18") (pin "8") (pinfunction "8_8") (pintype "power_in"))
    )
    (net (code "105") (name "Net-(D6-OUT8)") (class "Default")
      (node (ref "D6") (pin "13") (pinfunction "OUT8_13") (pintype "output"))
      (node (ref "X22") (pin "1") (pinfunction "1_1") (pintype "passive"))
    )
    (net (code "106") (name "Net-(D6-OUT9)") (class "Default")
      (node (ref "D6") (pin "14") (pinfunction "OUT9_14") (pintype "output"))
      (node (ref "X22") (pin "2") (pinfunction "2_2") (pintype "passive"))
    )
    (net (code "107") (name "Net-(D6-OUT10)") (class "Default")
      (node (ref "D6") (pin "15") (pinfunction "OUT10_15") (pintype "output"))
      (node (ref "X22") (pin "3") (pinfunction "3_3") (pintype "power_in"))
    )
    (net (code "108") (name "Net-(D6-OUT11)") (class "Default")
      (node (ref "D6") (pin "16") (pinfunction "OUT11_16") (pintype "output"))
      (node (ref "X22") (pin "4") (pinfunction "4_4") (pintype "power_in"))
    )
    (net (code "109") (name "Net-(D6-OUT12)") (class "Default")
      (node (ref "D6") (pin "17") (pinfunction "OUT12_17") (pintype "output"))
      (node (ref "X22") (pin "5") (pinfunction "5_5") (pintype "power_in"))
    )
    (net (code "110") (name "Net-(D6-OUT13)") (class "Default")
      (node (ref "D6") (pin "18") (pinfunction "OUT13_18") (pintype "output"))
      (node (ref "X22") (pin "6") (pinfunction "6_6") (pintype "power_in"))
    )
    (net (code "111") (name "Net-(D6-OUT14)") (class "Default")
      (node (ref "D6") (pin "19") (pinfunction "OUT14_19") (pintype "output"))
      (node (ref "X22") (pin "7") (pinfunction "7_7") (pintype "power_in"))
    )
    (net (code "112") (name "Net-(D6-OUT15)") (class "Default")
      (node (ref "D6") (pin "20") (pinfunction "OUT15_20") (pintype "output"))
      (node (ref "X22") (pin "8") (pinfunction "8_8") (pintype "power_in"))
    )
    (net (code "113") (name "Net-(D6-R-EXT)") (class "Default")
      (node (ref "D6") (pin "23") (pinfunction "R-EXT_23") (pintype "output"))
      (node (ref "R6") (pin "1") (pinfunction "1_1") (pintype "passive"))
    )
    (net (code "114") (name "Net-(D6-SDO)") (class "Default")
      (node (ref "D6") (pin "22") (pinfunction "SDO_22") (pintype "output"))
      (node (ref "D9") (pin "2") (pinfunction "SDI_2") (pintype "input"))
    )
    (net (code "115") (name "Net-(D7-OUT0)") (class "Default")
      (node (ref "D7") (pin "5") (pinfunction "OUT0_5") (pintype "output"))
      (node (ref "X23") (pin "1") (pinfunction "1_1") (pintype "passive"))
    )
    (net (code "116") (name "Net-(D7-OUT1)") (class "Default")
      (node (ref "D7") (pin "6") (pinfunction "OUT1_6") (pintype "output"))
      (node (ref "X23") (pin "2") (pinfunction "2_2") (pintype "passive"))
    )
    (net (code "117") (name "Net-(D7-OUT2)") (class "Default")
      (node (ref "D7") (pin "7") (pinfunction "OUT2_7") (pintype "output"))
      (node (ref "X23") (pin "3") (pinfunction "3_3") (pintype "power_in"))
    )
    (net (code "118") (name "Net-(D7-OUT3)") (class "Default")
      (node (ref "D7") (pin "8") (pinfunction "OUT3_8") (pintype "output"))
      (node (ref "X23") (pin "4") (pinfunction "4_4") (pintype "power_in"))
    )
    (net (code "119") (name "Net-(D7-OUT4)") (class "Default")
      (node (ref "D7") (pin "9") (pinfunction "OUT4_9") (pintype "output"))
      (node (ref "X23") (pin "5") (pinfunction "5_5") (pintype "power_in"))
    )
    (net (code "120") (name "Net-(D7-OUT5)") (class "Default")
      (node (ref "D7") (pin "10") (pinfunction "OUT5_10") (pintype "output"))
      (node (ref "X23") (pin "6") (pinfunction "6_6") (pintype "power_in"))
    )
    (net (code "121") (name "Net-(D7-OUT6)") (class "Default")
      (node (ref "D7") (pin "11") (pinfunction "OUT6_11") (pintype "output"))
      (node (ref "X23") (pin "7") (pinfunction "7_7") (pintype "power_in"))
    )
    (net (code "122") (name "Net-(D7-OUT7)") (class "Default")
      (node (ref "D7") (pin "12") (pinfunction "OUT7_12") (pintype "output"))
      (node (ref "X23") (pin "8") (pinfunction "8_8") (pintype "power_in"))
    )
    (net (code "123") (name "Net-(D7-OUT8)") (class "Default")
      (node (ref "D7") (pin "13") (pinfunction "OUT8_13") (pintype "output"))
      (node (ref "X27") (pin "1") (pinfunction "1_1") (pintype "passive"))
    )
    (net (code "124") (name "Net-(D7-OUT9)") (class "Default")
      (node (ref "D7") (pin "14") (pinfunction "OUT9_14") (pintype "output"))
      (node (ref "X27") (pin "2") (pinfunction "2_2") (pintype "passive"))
    )
    (net (code "125") (name "Net-(D7-OUT10)") (class "Default")
      (node (ref "D7") (pin "15") (pinfunction "OUT10_15") (pintype "output"))
      (node (ref "X27") (pin "3") (pinfunction "3_3") (pintype "power_in"))
    )
    (net (code "126") (name "Net-(D7-OUT11)") (class "Default")
      (node (ref "D7") (pin "16") (pinfunction "OUT11_16") (pintype "output"))
      (node (ref "X27") (pin "4") (pinfunction "4_4") (pintype "power_in"))
    )
    (net (code "127") (name "Net-(D7-OUT12)") (class "Default")
      (node (ref "D7") (pin "17") (pinfunction "OUT12_17") (pintype "output"))
      (node (ref "X27") (pin "5") (pinfunction "5_5") (pintype "power_in"))
    )
    (net (code "128") (name "Net-(D7-OUT13)") (class "Default")
      (node (ref "D7") (pin "18") (pinfunction "OUT13_18") (pintype "output"))
      (node (ref "X27") (pin "6") (pinfunction "6_6") (pintype "power_in"))
    )
    (net (code "129") (name "Net-(D7-OUT14)") (class "Default")
      (node (ref "D7") (pin "19") (pinfunction "OUT14_19") (pintype "output"))
      (node (ref "X27") (pin "7") (pinfunction "7_7") (pintype "power_in"))
    )
    (net (code "130") (name "Net-(D7-OUT15)") (class "Default")
      (node (ref "D7") (pin "20") (pinfunction "OUT15_20") (pintype "output"))
      (node (ref "X27") (pin "8") (pinfunction "8_8") (pintype "power_in"))
    )
    (net (code "131") (name "Net-(D7-R-EXT)") (class "Default")
      (node (ref "D7") (pin "23") (pinfunction "R-EXT_23") (pintype "output"))
      (node (ref "R7") (pin "1") (pinfunction "1_1") (pintype "passive"))
    )
    (net (code "132") (name "Net-(D8-OUT0)") (class "Default")
      (node (ref "D8") (pin "5") (pinfunction "OUT0_5") (pintype "output"))
      (node (ref "X24") (pin "1") (pinfunction "1_1") (pintype "passive"))
    )
    (net (code "133") (name "Net-(D8-OUT1)") (class "Default")
      (node (ref "D8") (pin "6") (pinfunction "OUT1_6") (pintype "output"))
      (node (ref "X24") (pin "2") (pinfunction "2_2") (pintype "passive"))
    )
    (net (code "134") (name "Net-(D8-OUT2)") (class "Default")
      (node (ref "D8") (pin "7") (pinfunction "OUT2_7") (pintype "output"))
      (node (ref "X24") (pin "3") (pinfunction "3_3") (pintype "power_in"))
    )
    (net (code "135") (name "Net-(D8-OUT3)") (class "Default")
      (node (ref "D8") (pin "8") (pinfunction "OUT3_8") (pintype "output"))
      (node (ref "X24") (pin "4") (pinfunction "4_4") (pintype "power_in"))
    )
    (net (code "136") (name "Net-(D8-OUT4)") (class "Default")
      (node (ref "D8") (pin "9") (pinfunction "OUT4_9") (pintype "output"))
      (node (ref "X24") (pin "5") (pinfunction "5_5") (pintype "power_in"))
    )
    (net (code "137") (name "Net-(D8-OUT5)") (class "Default")
      (node (ref "D8") (pin "10") (pinfunction "OUT5_10") (pintype "output"))
      (node (ref "X24") (pin "6") (pinfunction "6_6") (pintype "power_in"))
    )
    (net (code "138") (name "Net-(D8-OUT6)") (class "Default")
      (node (ref "D8") (pin "11") (pinfunction "OUT6_11") (pintype "output"))
      (node (ref "X24") (pin "7") (pinfunction "7_7") (pintype "power_in"))
    )
    (net (code "139") (name "Net-(D8-OUT7)") (class "Default")
      (node (ref "D8") (pin "12") (pinfunction "OUT7_12") (pintype "output"))
      (node (ref "X24") (pin "8") (pinfunction "8_8") (pintype "power_in"))
    )
    (net (code "140") (name "Net-(D8-OUT8)") (class "Default")
      (node (ref "D8") (pin "13") (pinfunction "OUT8_13") (pintype "output"))
      (node (ref "X28") (pin "1") (pinfunction "1_1") (pintype "passive"))
    )
    (net (code "141") (name "Net-(D8-OUT9)") (class "Default")
      (node (ref "D8") (pin "14") (pinfunction "OUT9_14") (pintype "output"))
      (node (ref "X28") (pin "2") (pinfunction "2_2") (pintype "passive"))
    )
    (net (code "142") (name "Net-(D8-OUT10)") (class "Default")
      (node (ref "D8") (pin "15") (pinfunction "OUT10_15") (pintype "output"))
      (node (ref "X28") (pin "3") (pinfunction "3_3") (pintype "power_in"))
    )
    (net (code "143") (name "Net-(D8-OUT11)") (class "Default")
      (node (ref "D8") (pin "16") (pinfunction "OUT11_16") (pintype "output"))
      (node (ref "X28") (pin "4") (pinfunction "4_4") (pintype "power_in"))
    )
    (net (code "144") (name "Net-(D8-OUT12)") (class "Default")
      (node (ref "D8") (pin "17") (pinfunction "OUT12_17") (pintype "output"))
      (node (ref "X28") (pin "5") (pinfunction "5_5") (pintype "power_in"))
    )
    (net (code "145") (name "Net-(D8-OUT13)") (class "Default")
      (node (ref "D8") (pin "18") (pinfunction "OUT13_18") (pintype "output"))
      (node (ref "X28") (pin "6") (pinfunction "6_6") (pintype "power_in"))
    )
    (net (code "146") (name "Net-(D8-OUT14)") (class "Default")
      (node (ref "D8") (pin "19") (pinfunction "OUT14_19") (pintype "output"))
      (node (ref "X28") (pin "7") (pinfunction "7_7") (pintype "power_in"))
    )
    (net (code "147") (name "Net-(D8-OUT15)") (class "Default")
      (node (ref "D8") (pin "20") (pinfunction "OUT15_20") (pintype "output"))
      (node (ref "X28") (pin "8") (pinfunction "8_8") (pintype "power_in"))
    )
    (net (code "148") (name "Net-(D8-R-EXT)") (class "Default")
      (node (ref "D8") (pin "23") (pinfunction "R-EXT_23") (pintype "output"))
      (node (ref "R8") (pin "1") (pinfunction "1_1") (pintype "passive"))
    )
    (net (code "149") (name "Net-(D9-OUT0)") (class "Default")
      (node (ref "D9") (pin "5") (pinfunction "OUT0_5") (pintype "output"))
      (node (ref "X26") (pin "1") (pinfunction "1_1") (pintype "passive"))
    )
    (net (code "150") (name "Net-(D9-OUT1)") (class "Default")
      (node (ref "D9") (pin "6") (pinfunction "OUT1_6") (pintype "output"))
      (node (ref "X26") (pin "2") (pinfunction "2_2") (pintype "passive"))
    )
    (net (code "151") (name "Net-(D9-OUT2)") (class "Default")
      (node (ref "D9") (pin "7") (pinfunction "OUT2_7") (pintype "output"))
      (node (ref "X26") (pin "3") (pinfunction "3_3") (pintype "power_in"))
    )
    (net (code "152") (name "Net-(D9-OUT3)") (class "Default")
      (node (ref "D9") (pin "8") (pinfunction "OUT3_8") (pintype "output"))
      (node (ref "X26") (pin "4") (pinfunction "4_4") (pintype "power_in"))
    )
    (net (code "153") (name "Net-(D9-OUT4)") (class "Default")
      (node (ref "D9") (pin "9") (pinfunction "OUT4_9") (pintype "output"))
      (node (ref "X26") (pin "5") (pinfunction "5_5") (pintype "power_in"))
    )
    (net (code "154") (name "Net-(D9-OUT5)") (class "Default")
      (node (ref "D9") (pin "10") (pinfunction "OUT5_10") (pintype "output"))
      (node (ref "X26") (pin "6") (pinfunction "6_6") (pintype "power_in"))
    )
    (net (code "155") (name "Net-(D9-OUT6)") (class "Default")
      (node (ref "D9") (pin "11") (pinfunction "OUT6_11") (pintype "output"))
      (node (ref "X26") (pin "7") (pinfunction "7_7") (pintype "power_in"))
    )
    (net (code "156") (name "Net-(D9-OUT7)") (class "Default")
      (node (ref "D9") (pin "12") (pinfunction "OUT7_12") (pintype "output"))
      (node (ref "X26") (pin "8") (pinfunction "8_8") (pintype "power_in"))
    )
    (net (code "157") (name "Net-(D9-OUT8)") (class "Default")
      (node (ref "D9") (pin "13") (pinfunction "OUT8_13") (pintype "output"))
      (node (ref "X29") (pin "1") (pinfunction "1_1") (pintype "passive"))
    )
    (net (code "158") (name "Net-(D9-OUT9)") (class "Default")
      (node (ref "D9") (pin "14") (pinfunction "OUT9_14") (pintype "output"))
      (node (ref "X29") (pin "2") (pinfunction "2_2") (pintype "passive"))
    )
    (net (code "159") (name "Net-(D9-OUT10)") (class "Default")
      (node (ref "D9") (pin "15") (pinfunction "OUT10_15") (pintype "output"))
      (node (ref "X29") (pin "3") (pinfunction "3_3") (pintype "power_in"))
    )
    (net (code "160") (name "Net-(D9-OUT11)") (class "Default")
      (node (ref "D9") (pin "16") (pinfunction "OUT11_16") (pintype "output"))
      (node (ref "X29") (pin "4") (pinfunction "4_4") (pintype "power_in"))
    )
    (net (code "161") (name "Net-(D9-OUT12)") (class "Default")
      (node (ref "D9") (pin "17") (pinfunction "OUT12_17") (pintype "output"))
      (node (ref "X29") (pin "5") (pinfunction "5_5") (pintype "power_in"))
    )
    (net (code "162") (name "Net-(D9-OUT13)") (class "Default")
      (node (ref "D9") (pin "18") (pinfunction "OUT13_18") (pintype "output"))
      (node (ref "X29") (pin "6") (pinfunction "6_6") (pintype "power_in"))
    )
    (net (code "163") (name "Net-(D9-OUT14)") (class "Default")
      (node (ref "D9") (pin "19") (pinfunction "OUT14_19") (pintype "output"))
      (node (ref "X29") (pin "7") (pinfunction "7_7") (pintype "power_in"))
    )
    (net (code "164") (name "Net-(D9-OUT15)") (class "Default")
      (node (ref "D9") (pin "20") (pinfunction "OUT15_20") (pintype "output"))
      (node (ref "X29") (pin "8") (pinfunction "8_8") (pintype "power_in"))
    )
    (net (code "165") (name "Net-(D9-R-EXT)") (class "Default")
      (node (ref "D9") (pin "23") (pinfunction "R-EXT_23") (pintype "output"))
      (node (ref "R9") (pin "1") (pinfunction "1_1") (pintype "passive"))
    )
    (net (code "166") (name "Net-(D10-OUT0)") (class "Default")
      (node (ref "D10") (pin "5") (pinfunction "OUT0_5") (pintype "output"))
      (node (ref "X30") (pin "1") (pinfunction "1_1") (pintype "passive"))
    )
    (net (code "167") (name "Net-(D10-OUT1)") (class "Default")
      (node (ref "D10") (pin "6") (pinfunction "OUT1_6") (pintype "output"))
      (node (ref "X30") (pin "2") (pinfunction "2_2") (pintype "passive"))
    )
    (net (code "168") (name "Net-(D10-OUT2)") (class "Default")
      (node (ref "D10") (pin "7") (pinfunction "OUT2_7") (pintype "output"))
      (node (ref "X30") (pin "3") (pinfunction "3_3") (pintype "power_in"))
    )
    (net (code "169") (name "Net-(D10-OUT3)") (class "Default")
      (node (ref "D10") (pin "8") (pinfunction "OUT3_8") (pintype "output"))
      (node (ref "X30") (pin "4") (pinfunction "4_4") (pintype "power_in"))
    )
    (net (code "170") (name "Net-(D10-OUT4)") (class "Default")
      (node (ref "D10") (pin "9") (pinfunction "OUT4_9") (pintype "output"))
      (node (ref "X30") (pin "5") (pinfunction "5_5") (pintype "power_in"))
    )
    (net (code "171") (name "Net-(D10-OUT5)") (class "Default")
      (node (ref "D10") (pin "10") (pinfunction "OUT5_10") (pintype "output"))
      (node (ref "X30") (pin "6") (pinfunction "6_6") (pintype "power_in"))
    )
    (net (code "172") (name "Net-(D10-OUT6)") (class "Default")
      (node (ref "D10") (pin "11") (pinfunction "OUT6_11") (pintype "output"))
      (node (ref "X30") (pin "7") (pinfunction "7_7") (pintype "power_in"))
    )
    (net (code "173") (name "Net-(D10-OUT7)") (class "Default")
      (node (ref "D10") (pin "12") (pinfunction "OUT7_12") (pintype "output"))
      (node (ref "X30") (pin "8") (pinfunction "8_8") (pintype "power_in"))
    )
    (net (code "174") (name "Net-(D10-OUT8)") (class "Default")
      (node (ref "D10") (pin "13") (pinfunction "OUT8_13") (pintype "output"))
      (node (ref "X34") (pin "1") (pinfunction "1_1") (pintype "passive"))
    )
    (net (code "175") (name "Net-(D10-OUT9)") (class "Default")
      (node (ref "D10") (pin "14") (pinfunction "OUT9_14") (pintype "output"))
      (node (ref "X34") (pin "2") (pinfunction "2_2") (pintype "passive"))
    )
    (net (code "176") (name "Net-(D10-OUT10)") (class "Default")
      (node (ref "D10") (pin "15") (pinfunction "OUT10_15") (pintype "output"))
      (node (ref "X34") (pin "3") (pinfunction "3_3") (pintype "power_in"))
    )
    (net (code "177") (name "Net-(D10-OUT11)") (class "Default")
      (node (ref "D10") (pin "16") (pinfunction "OUT11_16") (pintype "output"))
      (node (ref "X34") (pin "4") (pinfunction "4_4") (pintype "power_in"))
    )
    (net (code "178") (name "Net-(D10-OUT12)") (class "Default")
      (node (ref "D10") (pin "17") (pinfunction "OUT12_17") (pintype "output"))
      (node (ref "X34") (pin "5") (pinfunction "5_5") (pintype "power_in"))
    )
    (net (code "179") (name "Net-(D10-OUT13)") (class "Default")
      (node (ref "D10") (pin "18") (pinfunction "OUT13_18") (pintype "output"))
      (node (ref "X34") (pin "6") (pinfunction "6_6") (pintype "power_in"))
    )
    (net (code "180") (name "Net-(D10-OUT14)") (class "Default")
      (node (ref "D10") (pin "19") (pinfunction "OUT14_19") (pintype "output"))
      (node (ref "X34") (pin "7") (pinfunction "7_7") (pintype "power_in"))
    )
    (net (code "181") (name "Net-(D10-OUT15)") (class "Default")
      (node (ref "D10") (pin "20") (pinfunction "OUT15_20") (pintype "output"))
      (node (ref "X34") (pin "8") (pinfunction "8_8") (pintype "power_in"))
    )
    (net (code "182") (name "Net-(D10-R-EXT)") (class "Default")
      (node (ref "D10") (pin "23") (pinfunction "R-EXT_23") (pintype "output"))
      (node (ref "R10") (pin "1") (pinfunction "1_1") (pintype "passive"))
    )
    (net (code "183") (name "Net-(D10-SDI)") (class "Default")
      (node (ref "D10") (pin "2") (pinfunction "SDI_2") (pintype "input"))
      (node (ref "D7") (pin "22") (pinfunction "SDO_22") (pintype "output"))
    )
    (net (code "184") (name "Net-(D10-SDO)") (class "Default")
      (node (ref "D10") (pin "22") (pinfunction "SDO_22") (pintype "output"))
      (node (ref "D2") (pin "2") (pinfunction "SDI_2") (pintype "input"))
    )
    (net (code "185") (name "Net-(D11-OUT0)") (class "Default")
      (node (ref "D11") (pin "5") (pinfunction "OUT0_5") (pintype "output"))
      (node (ref "X31") (pin "1") (pinfunction "1_1") (pintype "passive"))
    )
    (net (code "186") (name "Net-(D11-OUT1)") (class "Default")
      (node (ref "D11") (pin "6") (pinfunction "OUT1_6") (pintype "output"))
      (node (ref "X31") (pin "2") (pinfunction "2_2") (pintype "passive"))
    )
    (net (code "187") (name "Net-(D11-OUT2)") (class "Default")
      (node (ref "D11") (pin "7") (pinfunction "OUT2_7") (pintype "output"))
      (node (ref "X31") (pin "3") (pinfunction "3_3") (pintype "power_in"))
    )
    (net (code "188") (name "Net-(D11-OUT3)") (class "Default")
      (node (ref "D11") (pin "8") (pinfunction "OUT3_8") (pintype "output"))
      (node (ref "X31") (pin "4") (pinfunction "4_4") (pintype "power_in"))
    )
    (net (code "189") (name "Net-(D11-OUT4)") (class "Default")
      (node (ref "D11") (pin "9") (pinfunction "OUT4_9") (pintype "output"))
      (node (ref "X31") (pin "5") (pinfunction "5_5") (pintype "power_in"))
    )
    (net (code "190") (name "Net-(D11-OUT5)") (class "Default")
      (node (ref "D11") (pin "10") (pinfunction "OUT5_10") (pintype "output"))
      (node (ref "X31") (pin "6") (pinfunction "6_6") (pintype "power_in"))
    )
    (net (code "191") (name "Net-(D11-OUT6)") (class "Default")
      (node (ref "D11") (pin "11") (pinfunction "OUT6_11") (pintype "output"))
      (node (ref "X31") (pin "7") (pinfunction "7_7") (pintype "power_in"))
    )
    (net (code "192") (name "Net-(D11-OUT7)") (class "Default")
      (node (ref "D11") (pin "12") (pinfunction "OUT7_12") (pintype "output"))
      (node (ref "X31") (pin "8") (pinfunction "8_8") (pintype "power_in"))
    )
    (net (code "193") (name "Net-(D11-OUT8)") (class "Default")
      (node (ref "D11") (pin "13") (pinfunction "OUT8_13") (pintype "output"))
      (node (ref "X35") (pin "1") (pinfunction "1_1") (pintype "passive"))
    )
    (net (code "194") (name "Net-(D11-OUT9)") (class "Default")
      (node (ref "D11") (pin "14") (pinfunction "OUT9_14") (pintype "output"))
      (node (ref "X35") (pin "2") (pinfunction "2_2") (pintype "passive"))
    )
    (net (code "195") (name "Net-(D11-OUT10)") (class "Default")
      (node (ref "D11") (pin "15") (pinfunction "OUT10_15") (pintype "output"))
      (node (ref "X35") (pin "3") (pinfunction "3_3") (pintype "power_in"))
    )
    (net (code "196") (name "Net-(D11-OUT11)") (class "Default")
      (node (ref "D11") (pin "16") (pinfunction "OUT11_16") (pintype "output"))
      (node (ref "X35") (pin "4") (pinfunction "4_4") (pintype "power_in"))
    )
    (net (code "197") (name "Net-(D11-OUT12)") (class "Default")
      (node (ref "D11") (pin "17") (pinfunction "OUT12_17") (pintype "output"))
      (node (ref "X35") (pin "5") (pinfunction "5_5") (pintype "power_in"))
    )
    (net (code "198") (name "Net-(D11-OUT13)") (class "Default")
      (node (ref "D11") (pin "18") (pinfunction "OUT13_18") (pintype "output"))
      (node (ref "X35") (pin "6") (pinfunction "6_6") (pintype "power_in"))
    )
    (net (code "199") (name "Net-(D11-OUT14)") (class "Default")
      (node (ref "D11") (pin "19") (pinfunction "OUT14_19") (pintype "output"))
      (node (ref "X35") (pin "7") (pinfunction "7_7") (pintype "power_in"))
    )
    (net (code "200") (name "Net-(D11-OUT15)") (class "Default")
      (node (ref "D11") (pin "20") (pinfunction "OUT15_20") (pintype "output"))
      (node (ref "X35") (pin "8") (pinfunction "8_8") (pintype "power_in"))
    )
    (net (code "201") (name "Net-(D11-R-EXT)") (class "Default")
      (node (ref "D11") (pin "23") (pinfunction "R-EXT_23") (pintype "output"))
      (node (ref "R11") (pin "1") (pinfunction "1_1") (pintype "passive"))
    )
    (net (code "202") (name "Net-(D11-SDI)") (class "Default")
      (node (ref "D11") (pin "2") (pinfunction "SDI_2") (pintype "input"))
      (node (ref "D8") (pin "22") (pinfunction "SDO_22") (pintype "output"))
    )
    (net (code "203") (name "Net-(D11-SDO)") (class "Default")
      (node (ref "D11") (pin "22") (pinfunction "SDO_22") (pintype "output"))
      (node (ref "D3") (pin "2") (pinfunction "SDI_2") (pintype "input"))
    )
    (net (code "204") (name "Net-(D12-OUT0)") (class "Default")
      (node (ref "D12") (pin "5") (pinfunction "OUT0_5") (pintype "output"))
      (node (ref "X32") (pin "1") (pinfunction "1_1") (pintype "passive"))
    )
    (net (code "205") (name "Net-(D12-OUT1)") (class "Default")
      (node (ref "D12") (pin "6") (pinfunction "OUT1_6") (pintype "output"))
      (node (ref "X32") (pin "2") (pinfunction "2_2") (pintype "passive"))
    )
    (net (code "206") (name "Net-(D12-OUT2)") (class "Default")
      (node (ref "D12") (pin "7") (pinfunction "OUT2_7") (pintype "output"))
      (node (ref "X32") (pin "3") (pinfunction "3_3") (pintype "power_in"))
    )
    (net (code "207") (name "Net-(D12-OUT3)") (class "Default")
      (node (ref "D12") (pin "8") (pinfunction "OUT3_8") (pintype "output"))
      (node (ref "X32") (pin "4") (pinfunction "4_4") (pintype "power_in"))
    )
    (net (code "208") (name "Net-(D12-OUT4)") (class "Default")
      (node (ref "D12") (pin "9") (pinfunction "OUT4_9") (pintype "output"))
      (node (ref "X32") (pin "5") (pinfunction "5_5") (pintype "power_in"))
    )
    (net (code "209") (name "Net-(D12-OUT5)") (class "Default")
      (node (ref "D12") (pin "10") (pinfunction "OUT5_10") (pintype "output"))
      (node (ref "X32") (pin "6") (pinfunction "6_6") (pintype "power_in"))
    )
    (net (code "210") (name "Net-(D12-OUT6)") (class "Default")
      (node (ref "D12") (pin "11") (pinfunction "OUT6_11") (pintype "output"))
      (node (ref "X32") (pin "7") (pinfunction "7_7") (pintype "power_in"))
    )
    (net (code "211") (name "Net-(D12-OUT7)") (class "Default")
      (node (ref "D12") (pin "12") (pinfunction "OUT7_12") (pintype "output"))
      (node (ref "X32") (pin "8") (pinfunction "8_8") (pintype "power_in"))
    )
    (net (code "212") (name "Net-(D12-OUT8)") (class "Default")
      (node (ref "D12") (pin "13") (pinfunction "OUT8_13") (pintype "output"))
      (node (ref "X36") (pin "1") (pinfunction "1_1") (pintype "passive"))
    )
    (net (code "213") (name "Net-(D12-OUT9)") (class "Default")
      (node (ref "D12") (pin "14") (pinfunction "OUT9_14") (pintype "output"))
      (node (ref "X36") (pin "2") (pinfunction "2_2") (pintype "passive"))
    )
    (net (code "214") (name "Net-(D12-OUT10)") (class "Default")
      (node (ref "D12") (pin "15") (pinfunction "OUT10_15") (pintype "output"))
      (node (ref "X36") (pin "3") (pinfunction "3_3") (pintype "power_in"))
    )
    (net (code "215") (name "Net-(D12-OUT11)") (class "Default")
      (node (ref "D12") (pin "16") (pinfunction "OUT11_16") (pintype "output"))
      (node (ref "X36") (pin "4") (pinfunction "4_4") (pintype "power_in"))
    )
    (net (code "216") (name "Net-(D12-OUT12)") (class "Default")
      (node (ref "D12") (pin "17") (pinfunction "OUT12_17") (pintype "output"))
      (node (ref "X36") (pin "5") (pinfunction "5_5") (pintype "power_in"))
    )
    (net (code "217") (name "Net-(D12-OUT13)") (class "Default")
      (node (ref "D12") (pin "18") (pinfunction "OUT13_18") (pintype "output"))
      (node (ref "X36") (pin "6") (pinfunction "6_6") (pintype "power_in"))
    )
    (net (code "218") (name "Net-(D12-OUT14)") (class "Default")
      (node (ref "D12") (pin "19") (pinfunction "OUT14_19") (pintype "output"))
      (node (ref "X36") (pin "7") (pinfunction "7_7") (pintype "power_in"))
    )
    (net (code "219") (name "Net-(D12-OUT15)") (class "Default")
      (node (ref "D12") (pin "20") (pinfunction "OUT15_20") (pintype "output"))
      (node (ref "X36") (pin "8") (pinfunction "8_8") (pintype "power_in"))
    )
    (net (code "220") (name "Net-(D12-R-EXT)") (class "Default")
      (node (ref "D12") (pin "23") (pinfunction "R-EXT_23") (pintype "output"))
      (node (ref "R12") (pin "1") (pinfunction "1_1") (pintype "passive"))
    )
    (net (code "221") (name "Net-(D12-SDI)") (class "Default")
      (node (ref "D12") (pin "2") (pinfunction "SDI_2") (pintype "input"))
      (node (ref "D9") (pin "22") (pinfunction "SDO_22") (pintype "output"))
    )
    (net (code "222") (name "Net-(X1-Pad2)") (class "Default")
      (node (ref "X1") (pin "2") (pinfunction "2_2") (pintype "passive"))
      (node (ref "X4") (pin "4") (pinfunction "4_4") (pintype "power_in"))
    )
    (net (code "223") (name "Net-(X3-Pad5)") (class "Default")
      (node (ref "X3") (pin "5") (pinfunction "5_5") (pintype "power_in"))
      (node (ref "X5") (pin "1") (pinfunction "1_1") (pintype "passive"))
    )
    (net (code "224") (name "Net-(X3-Pad6)") (class "Default")
      (node (ref "X3") (pin "6") (pinfunction "6_6") (pintype "power_in"))
      (node (ref "X5") (pin "2") (pinfunction "2_2") (pintype "passive"))
    )
    (net (code "225") (name "Net-(X3-Pad7)") (class "Default")
      (node (ref "X3") (pin "7") (pinfunction "7_7") (pintype "power_in"))
      (node (ref "X5") (pin "3") (pinfunction "3_3") (pintype "power_in"))
    )
    (net (code "226") (name "Net-(X3-Pad8)") (class "Default")
      (node (ref "X3") (pin "8") (pinfunction "8_8") (pintype "power_in"))
      (node (ref "X5") (pin "4") (pinfunction "4_4") (pintype "power_in"))
    )
    (net (code "227") (name "Net-(X3-Pad9)") (class "Default")
      (node (ref "X3") (pin "9") (pinfunction "9_9") (pintype "power_in"))
      (node (ref "X5") (pin "5") (pinfunction "5_5") (pintype "power_in"))
    )
    (net (code "228") (name "Net-(X3-Pad10)") (class "Default")
      (node (ref "X3") (pin "10") (pinfunction "10_10") (pintype "power_in"))
      (node (ref "X5") (pin "6") (pinfunction "6_6") (pintype "power_in"))
    )
    (net (code "229") (name "Net-(X3-Pad11)") (class "Default")
      (node (ref "X3") (pin "11") (pinfunction "11_11") (pintype "power_in"))
      (node (ref "X5") (pin "7") (pinfunction "7_7") (pintype "power_in"))
    )
    (net (code "230") (name "Net-(X3-Pad12)") (class "Default")
      (node (ref "X3") (pin "12") (pinfunction "12_12") (pintype "power_in"))
      (node (ref "X5") (pin "8") (pinfunction "8_8") (pintype "power_in"))
    )
    (net (code "231") (name "Net-(X3-Pad13)") (class "Default")
      (node (ref "X3") (pin "13") (pinfunction "13_13") (pintype "power_in"))
      (node (ref "X5") (pin "9") (pinfunction "9_9") (pintype "power_in"))
    )
    (net (code "232") (name "Net-(X3-Pad14)") (class "Default")
      (node (ref "X3") (pin "14") (pinfunction "14_14") (pintype "power_in"))
      (node (ref "X5") (pin "10") (pinfunction "10_10") (pintype "power_in"))
    )
    (net (code "233") (name "Net-(X3-Pad15)") (class "Default")
      (node (ref "X3") (pin "15") (pinfunction "15_15") (pintype "power_in"))
      (node (ref "X5") (pin "11") (pinfunction "11_11") (pintype "power_in"))
    )
    (net (code "234") (name "Net-(X3-Pad16)") (class "Default")
      (node (ref "X3") (pin "16") (pinfunction "16_16") (pintype "power_in"))
      (node (ref "X5") (pin "12") (pinfunction "12_12") (pintype "power_in"))
    )
    (net (code "235") (name "Net-(X3-Pad17)") (class "Default")
      (node (ref "X3") (pin "17") (pinfunction "17_17") (pintype "power_in"))
      (node (ref "X5") (pin "13") (pinfunction "13_13") (pintype "power_in"))
    )
    (net (code "236") (name "Net-(X3-Pad18)") (class "Default")
      (node (ref "X3") (pin "18") (pinfunction "18_18") (pintype "power_in"))
      (node (ref "X5") (pin "14") (pinfunction "14_14") (pintype "power_in"))
    )
    (net (code "237") (name "Net-(X4-Pad5)") (class "Default")
      (node (ref "X4") (pin "5") (pinfunction "5_5") (pintype "power_in"))
      (node (ref "X6") (pin "1") (pinfunction "1_1") (pintype "passive"))
    )
    (net (code "238") (name "Net-(X4-Pad6)") (class "Default")
      (node (ref "X4") (pin "6") (pinfunction "6_6") (pintype "power_in"))
      (node (ref "X6") (pin "2") (pinfunction "2_2") (pintype "passive"))
    )
    (net (code "239") (name "Net-(X4-Pad7)") (class "Default")
      (node (ref "X4") (pin "7") (pinfunction "7_7") (pintype "power_in"))
      (node (ref "X6") (pin "3") (pinfunction "3_3") (pintype "power_in"))
    )
    (net (code "240") (name "Net-(X4-Pad8)") (class "Default")
      (node (ref "X4") (pin "8") (pinfunction "8_8") (pintype "power_in"))
      (node (ref "X6") (pin "4") (pinfunction "4_4") (pintype "power_in"))
    )
    (net (code "241") (name "Net-(X4-Pad9)") (class "Default")
      (node (ref "X4") (pin "9") (pinfunction "9_9") (pintype "power_in"))
      (node (ref "X6") (pin "5") (pinfunction "5_5") (pintype "power_in"))
    )
    (net (code "242") (name "Net-(X4-Pad10)") (class "Default")
      (node (ref "X4") (pin "10") (pinfunction "10_10") (pintype "power_in"))
      (node (ref "X6") (pin "6") (pinfunction "6_6") (pintype "power_in"))
    )
    (net (code "243") (name "Net-(X4-Pad11)") (class "Default")
      (node (ref "X4") (pin "11") (pinfunction "11_11") (pintype "power_in"))
      (node (ref "X6") (pin "7") (pinfunction "7_7") (pintype "power_in"))
    )
    (net (code "244") (name "Net-(X4-Pad12)") (class "Default")
      (node (ref "X4") (pin "12") (pinfunction "12_12") (pintype "power_in"))
      (node (ref "X6") (pin "8") (pinfunction "8_8") (pintype "power_in"))
    )
    (net (code "245") (name "Net-(X4-Pad13)") (class "Default")
      (node (ref "X4") (pin "13") (pinfunction "13_13") (pintype "power_in"))
      (node (ref "X6") (pin "9") (pinfunction "9_9") (pintype "power_in"))
    )
    (net (code "246") (name "Net-(X4-Pad14)") (class "Default")
      (node (ref "X4") (pin "14") (pinfunction "14_14") (pintype "power_in"))
      (node (ref "X6") (pin "10") (pinfunction "10_10") (pintype "power_in"))
    )
    (net (code "247") (name "Net-(X4-Pad15)") (class "Default")
      (node (ref "X4") (pin "15") (pinfunction "15_15") (pintype "power_in"))
      (node (ref "X6") (pin "11") (pinfunction "11_11") (pintype "power_in"))
    )
    (net (code "248") (name "Net-(X4-Pad16)") (class "Default")
      (node (ref "X4") (pin "16") (pinfunction "16_16") (pintype "power_in"))
      (node (ref "X6") (pin "12") (pinfunction "12_12") (pintype "power_in"))
    )
    (net (code "249") (name "Net-(X4-Pad17)") (class "Default")
      (node (ref "X4") (pin "17") (pinfunction "17_17") (pintype "power_in"))
      (node (ref "X6") (pin "13") (pinfunction "13_13") (pintype "power_in"))
    )
    (net (code "250") (name "Net-(X4-Pad18)") (class "Default")
      (node (ref "X4") (pin "18") (pinfunction "18_18") (pintype "power_in"))
      (node (ref "X6") (pin "14") (pinfunction "14_14") (pintype "power_in"))
    )
    (net (code "251") (name "Net-(X4-Pad19)") (class "Default")
      (node (ref "X4") (pin "19") (pinfunction "19_19") (pintype "power_in"))
      (node (ref "X6") (pin "15") (pinfunction "15_15") (pintype "power_in"))
    )
    (net (code "252") (name "Net-(X4-Pad20)") (class "Default")
      (node (ref "X4") (pin "20") (pinfunction "20_20") (pintype "power_in"))
      (node (ref "X6") (pin "16") (pinfunction "16_16") (pintype "power_in"))
    )
    (net (code "253") (name "unconnected-(D1-GCLK-Pad21)") (class "Default")
      (node (ref "D1") (pin "21") (pinfunction "GCLK_21") (pintype "input"))
    )
    (net (code "254") (name "unconnected-(D2-GCLK-Pad21)") (class "Default")
      (node (ref "D2") (pin "21") (pinfunction "GCLK_21") (pintype "input"))
    )
    (net (code "255") (name "unconnected-(D3-GCLK-Pad21)") (class "Default")
      (node (ref "D3") (pin "21") (pinfunction "GCLK_21") (pintype "input"))
    )
    (net (code "256") (name "unconnected-(D4-GCLK-Pad21)") (class "Default")
      (node (ref "D4") (pin "21") (pinfunction "GCLK_21") (pintype "input"))
    )
    (net (code "257") (name "unconnected-(D5-GCLK-Pad21)") (class "Default")
      (node (ref "D5") (pin "21") (pinfunction "GCLK_21") (pintype "input"))
    )
    (net (code "258") (name "unconnected-(D6-GCLK-Pad21)") (class "Default")
      (node (ref "D6") (pin "21") (pinfunction "GCLK_21") (pintype "input"))
    )
    (net (code "259") (name "unconnected-(D7-GCLK-Pad21)") (class "Default")
      (node (ref "D7") (pin "21") (pinfunction "GCLK_21") (pintype "input"))
    )
    (net (code "260") (name "unconnected-(D8-GCLK-Pad21)") (class "Default")
      (node (ref "D8") (pin "21") (pinfunction "GCLK_21") (pintype "input"))
    )
    (net (code "261") (name "unconnected-(D9-GCLK-Pad21)") (class "Default")
      (node (ref "D9") (pin "21") (pinfunction "GCLK_21") (pintype "input"))
    )
    (net (code "262") (name "unconnected-(D10-GCLK-Pad21)") (class "Default")
      (node (ref "D10") (pin "21") (pinfunction "GCLK_21") (pintype "input"))
    )
    (net (code "263") (name "unconnected-(D11-GCLK-Pad21)") (class "Default")
      (node (ref "D11") (pin "21") (pinfunction "GCLK_21") (pintype "input"))
    )
    (net (code "264") (name "unconnected-(D12-GCLK-Pad21)") (class "Default")
      (node (ref "D12") (pin "21") (pinfunction "GCLK_21") (pintype "input"))
    )
    (net (code "265") (name "unconnected-(D12-SDO-Pad22)") (class "Default")
      (node (ref "D12") (pin "22") (pinfunction "SDO_22") (pintype "output"))
    )
  )
)
